# PCB_3U_BNC.net
KiCad netlist of a schematic drawn in Altium Designer
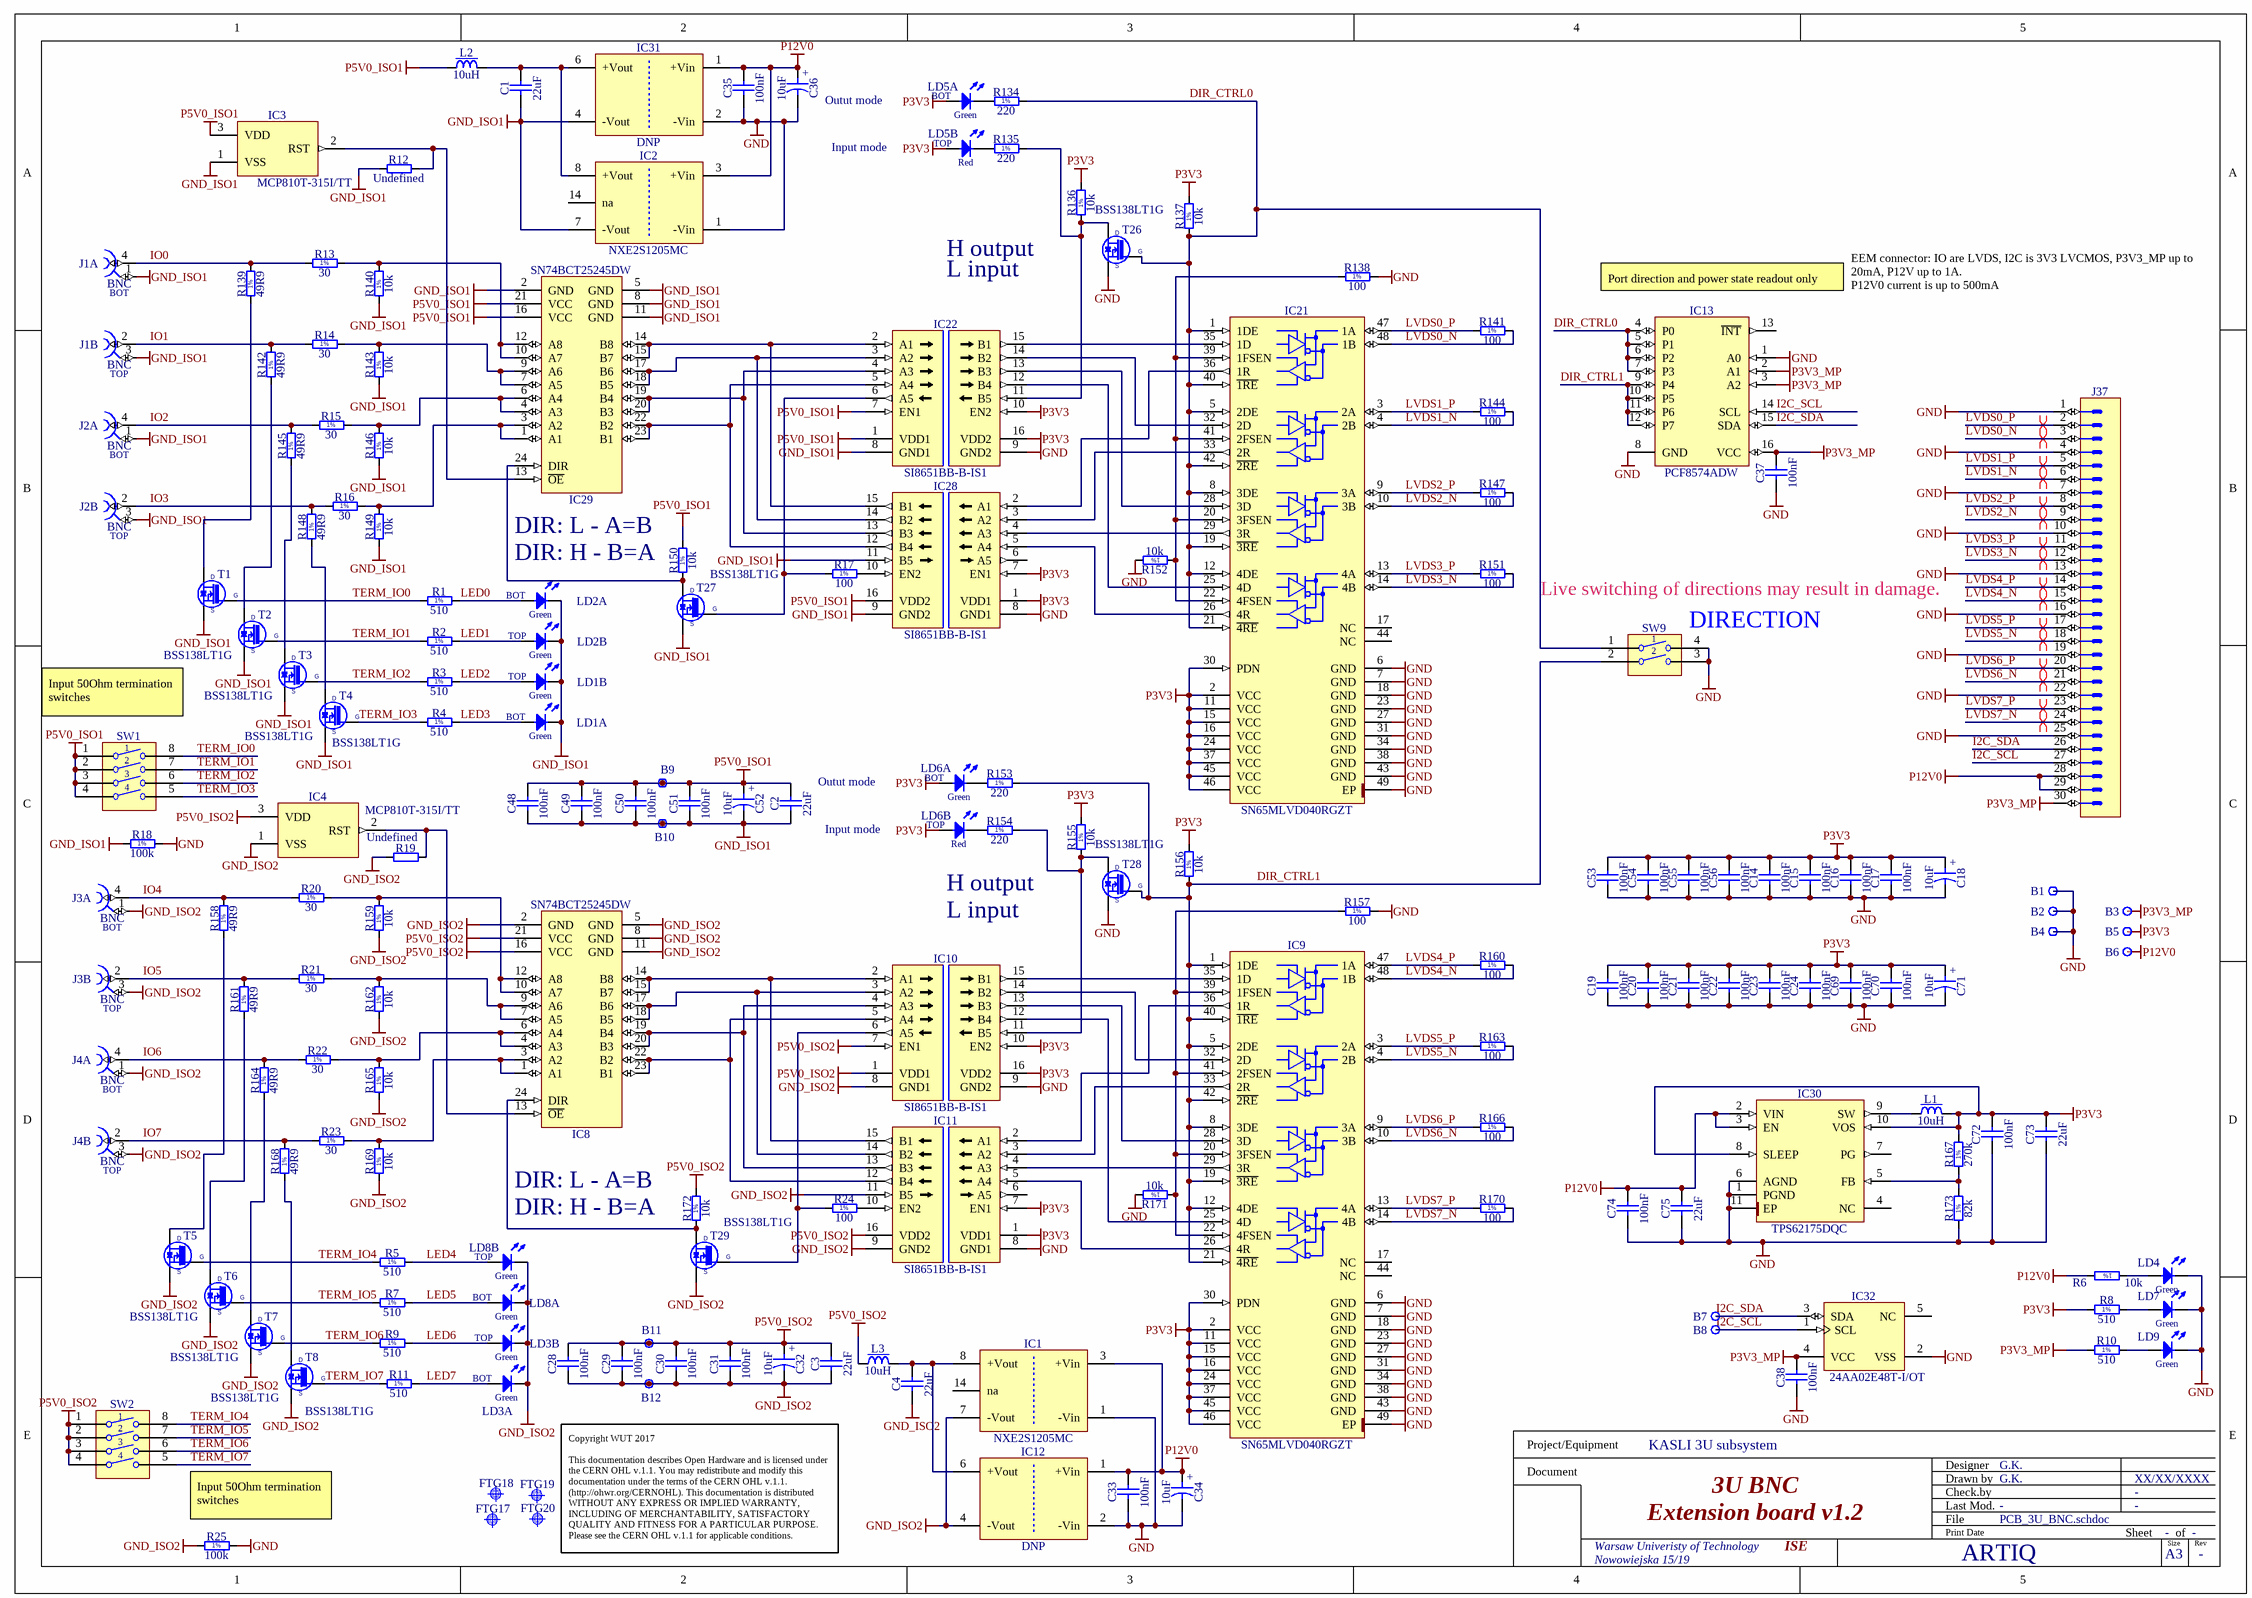
[diagram p0: PCB_3U_BNC.schdoc]

(export (version "E")
  (design (tool "Eeschema 10.0.6"))
  (components
    (comp (ref "B1")
      (value "Plated Hole")
      (footprint "c130h60")
      (description "Single Terminal Socket")
      (fields (field (name "PART NUMBER") "PLATED_HOLE0.6_PAD1.3") (field (name "AUTHOR") "CERN DEM MR"))
      (libsource (lib "Eletro-mechanical") (part "Single Terminal Socket"))
    )
    (comp (ref "B2")
      (value "Plated Hole")
      (footprint "c130h60")
      (description "Single Terminal Socket")
      (fields (field (name "PART NUMBER") "PLATED_HOLE0.6_PAD1.3") (field (name "AUTHOR") "CERN DEM MR"))
      (libsource (lib "Eletro-mechanical") (part "Single Terminal Socket"))
    )
    (comp (ref "B3")
      (value "Plated Hole")
      (footprint "c130h60")
      (description "Single Terminal Socket")
      (fields (field (name "PART NUMBER") "PLATED_HOLE0.6_PAD1.3") (field (name "AUTHOR") "CERN DEM MR"))
      (libsource (lib "Eletro-mechanical") (part "Single Terminal Socket"))
    )
    (comp (ref "B4")
      (value "Plated Hole")
      (footprint "c130h60")
      (description "Single Terminal Socket")
      (fields (field (name "PART NUMBER") "PLATED_HOLE0.6_PAD1.3") (field (name "AUTHOR") "CERN DEM MR"))
      (libsource (lib "Eletro-mechanical") (part "Single Terminal Socket"))
    )
    (comp (ref "B5")
      (value "Plated Hole")
      (footprint "c130h60")
      (description "Single Terminal Socket")
      (fields (field (name "PART NUMBER") "PLATED_HOLE0.6_PAD1.3") (field (name "AUTHOR") "CERN DEM MR"))
      (libsource (lib "Eletro-mechanical") (part "Single Terminal Socket"))
    )
    (comp (ref "B6")
      (value "Plated Hole")
      (footprint "c130h60")
      (description "Single Terminal Socket")
      (fields (field (name "PART NUMBER") "PLATED_HOLE0.6_PAD1.3") (field (name "AUTHOR") "CERN DEM MR"))
      (libsource (lib "Eletro-mechanical") (part "Single Terminal Socket"))
    )
    (comp (ref "B7")
      (value "Plated Hole")
      (footprint "c130h60")
      (description "Single Terminal Socket")
      (fields (field (name "PART NUMBER") "PLATED_HOLE0.6_PAD1.3") (field (name "AUTHOR") "CERN DEM MR"))
      (libsource (lib "Eletro-mechanical") (part "Single Terminal Socket"))
    )
    (comp (ref "B8")
      (value "Plated Hole")
      (footprint "c130h60")
      (description "Single Terminal Socket")
      (fields (field (name "PART NUMBER") "PLATED_HOLE0.6_PAD1.3") (field (name "AUTHOR") "CERN DEM MR"))
      (libsource (lib "Eletro-mechanical") (part "Single Terminal Socket"))
    )
    (comp (ref "B9")
      (value "Plated Hole")
      (footprint "c130h60")
      (description "Single Terminal Socket")
      (fields (field (name "PART NUMBER") "PLATED_HOLE0.6_PAD1.3") (field (name "AUTHOR") "CERN DEM MR"))
      (libsource (lib "Eletro-mechanical") (part "Single Terminal Socket"))
    )
    (comp (ref "B10")
      (value "Plated Hole")
      (footprint "c130h60")
      (description "Single Terminal Socket")
      (fields (field (name "PART NUMBER") "PLATED_HOLE0.6_PAD1.3") (field (name "AUTHOR") "CERN DEM MR"))
      (libsource (lib "Eletro-mechanical") (part "Single Terminal Socket"))
    )
    (comp (ref "B11")
      (value "Plated Hole")
      (footprint "c130h60")
      (description "Single Terminal Socket")
      (fields (field (name "PART NUMBER") "PLATED_HOLE0.6_PAD1.3") (field (name "AUTHOR") "CERN DEM MR"))
      (libsource (lib "Eletro-mechanical") (part "Single Terminal Socket"))
    )
    (comp (ref "B12")
      (value "Plated Hole")
      (footprint "c130h60")
      (description "Single Terminal Socket")
      (fields (field (name "PART NUMBER") "PLATED_HOLE0.6_PAD1.3") (field (name "AUTHOR") "CERN DEM MR"))
      (libsource (lib "Eletro-mechanical") (part "Single Terminal Socket"))
    )
    (comp (ref "C1")
      (value "22uF")
      (footprint "CAPC2012X135N")
      (description "Non-polarised capacitor")
      (fields
        (field (name "PART NUMBER") "CC0805_22UF_16V_10%_X5R")
        (field (name "VOLTAGE") "16V")
        (field (name "AUTHOR") "CERN DEM JLC")
      )
      (libsource (lib "Capacitors") (part "Capacitor - non polarized"))
    )
    (comp (ref "C2")
      (value "22uF")
      (footprint "CAPC2012X135N")
      (description "Non-polarised capacitor")
      (fields
        (field (name "PART NUMBER") "CC0805_22UF_16V_10%_X5R")
        (field (name "VOLTAGE") "16V")
        (field (name "AUTHOR") "CERN DEM JLC")
      )
      (libsource (lib "Capacitors") (part "Capacitor - non polarized"))
    )
    (comp (ref "C3")
      (value "22uF")
      (footprint "CAPC2012X135N")
      (description "Non-polarised capacitor")
      (fields
        (field (name "PART NUMBER") "CC0805_22UF_16V_10%_X5R")
        (field (name "VOLTAGE") "16V")
        (field (name "AUTHOR") "CERN DEM JLC")
      )
      (libsource (lib "Capacitors") (part "Capacitor - non polarized"))
    )
    (comp (ref "C4")
      (value "22uF")
      (footprint "CAPC2012X135N")
      (description "Non-polarised capacitor")
      (fields
        (field (name "PART NUMBER") "CC0805_22UF_16V_10%_X5R")
        (field (name "VOLTAGE") "16V")
        (field (name "AUTHOR") "CERN DEM JLC")
      )
      (libsource (lib "Capacitors") (part "Capacitor - non polarized"))
    )
    (comp (ref "C14")
      (value "100nF")
      (footprint "CAPC1005X55N")
      (description "Non-polarised capacitor")
      (fields
        (field (name "PART NUMBER") "CC0402_100NF_16V_10%_X5R")
        (field (name "VOLTAGE") "16V")
        (field (name "AUTHOR") "CERN DEM JLC")
      )
      (libsource (lib "Capacitors") (part "Capacitor - non polarized"))
    )
    (comp (ref "C15")
      (value "100nF")
      (footprint "CAPC1005X55N")
      (description "Non-polarised capacitor")
      (fields
        (field (name "PART NUMBER") "CC0402_100NF_16V_10%_X5R")
        (field (name "VOLTAGE") "16V")
        (field (name "AUTHOR") "CERN DEM JLC")
      )
      (libsource (lib "Capacitors") (part "Capacitor - non polarized"))
    )
    (comp (ref "C16")
      (value "100nF")
      (footprint "CAPC1005X55N")
      (description "Non-polarised capacitor")
      (fields
        (field (name "PART NUMBER") "CC0402_100NF_16V_10%_X5R")
        (field (name "VOLTAGE") "16V")
        (field (name "AUTHOR") "CERN DEM JLC")
      )
      (libsource (lib "Capacitors") (part "Capacitor - non polarized"))
    )
    (comp (ref "C17")
      (value "100nF")
      (footprint "CAPC1005X55N")
      (description "Non-polarised capacitor")
      (fields
        (field (name "PART NUMBER") "CC0402_100NF_16V_10%_X5R")
        (field (name "VOLTAGE") "16V")
        (field (name "AUTHOR") "CERN DEM JLC")
      )
      (libsource (lib "Capacitors") (part "Capacitor - non polarized"))
    )
    (comp (ref "C18")
      (value "10uF")
      (footprint "CAPAE430X540N")
      (description "Polarised capacitor")
      (fields
        (field (name "PART NUMBER") "CAE430-540_10UF_16V_20%")
        (field (name "VOLTAGE") "16V")
        (field (name "AUTHOR") "CERN DEM JLC")
      )
      (libsource (lib "Capacitors") (part "Capacitor - polarized"))
    )
    (comp (ref "C19")
      (value "100nF")
      (footprint "CAPC1005X55N")
      (description "Non-polarised capacitor")
      (fields
        (field (name "PART NUMBER") "CC0402_100NF_16V_10%_X5R")
        (field (name "VOLTAGE") "16V")
        (field (name "AUTHOR") "CERN DEM JLC")
      )
      (libsource (lib "Capacitors") (part "Capacitor - non polarized"))
    )
    (comp (ref "C20")
      (value "100nF")
      (footprint "CAPC1005X55N")
      (description "Non-polarised capacitor")
      (fields
        (field (name "PART NUMBER") "CC0402_100NF_16V_10%_X5R")
        (field (name "VOLTAGE") "16V")
        (field (name "AUTHOR") "CERN DEM JLC")
      )
      (libsource (lib "Capacitors") (part "Capacitor - non polarized"))
    )
    (comp (ref "C21")
      (value "100nF")
      (footprint "CAPC1005X55N")
      (description "Non-polarised capacitor")
      (fields
        (field (name "PART NUMBER") "CC0402_100NF_16V_10%_X5R")
        (field (name "VOLTAGE") "16V")
        (field (name "AUTHOR") "CERN DEM JLC")
      )
      (libsource (lib "Capacitors") (part "Capacitor - non polarized"))
    )
    (comp (ref "C22")
      (value "100nF")
      (footprint "CAPC1005X55N")
      (description "Non-polarised capacitor")
      (fields
        (field (name "PART NUMBER") "CC0402_100NF_16V_10%_X5R")
        (field (name "VOLTAGE") "16V")
        (field (name "AUTHOR") "CERN DEM JLC")
      )
      (libsource (lib "Capacitors") (part "Capacitor - non polarized"))
    )
    (comp (ref "C23")
      (value "100nF")
      (footprint "CAPC1005X55N")
      (description "Non-polarised capacitor")
      (fields
        (field (name "PART NUMBER") "CC0402_100NF_16V_10%_X5R")
        (field (name "VOLTAGE") "16V")
        (field (name "AUTHOR") "CERN DEM JLC")
      )
      (libsource (lib "Capacitors") (part "Capacitor - non polarized"))
    )
    (comp (ref "C24")
      (value "100nF")
      (footprint "CAPC1005X55N")
      (description "Non-polarised capacitor")
      (fields
        (field (name "PART NUMBER") "CC0402_100NF_16V_10%_X5R")
        (field (name "VOLTAGE") "16V")
        (field (name "AUTHOR") "CERN DEM JLC")
      )
      (libsource (lib "Capacitors") (part "Capacitor - non polarized"))
    )
    (comp (ref "C28")
      (value "100nF")
      (footprint "CAPC1005X55N")
      (description "Non-polarised capacitor")
      (fields
        (field (name "PART NUMBER") "CC0402_100NF_16V_10%_X5R")
        (field (name "VOLTAGE") "16V")
        (field (name "AUTHOR") "CERN DEM JLC")
      )
      (libsource (lib "Capacitors") (part "Capacitor - non polarized"))
    )
    (comp (ref "C29")
      (value "100nF")
      (footprint "CAPC1005X55N")
      (description "Non-polarised capacitor")
      (fields
        (field (name "PART NUMBER") "CC0402_100NF_16V_10%_X5R")
        (field (name "VOLTAGE") "16V")
        (field (name "AUTHOR") "CERN DEM JLC")
      )
      (libsource (lib "Capacitors") (part "Capacitor - non polarized"))
    )
    (comp (ref "C30")
      (value "100nF")
      (footprint "CAPC1005X55N")
      (description "Non-polarised capacitor")
      (fields
        (field (name "PART NUMBER") "CC0402_100NF_16V_10%_X5R")
        (field (name "VOLTAGE") "16V")
        (field (name "AUTHOR") "CERN DEM JLC")
      )
      (libsource (lib "Capacitors") (part "Capacitor - non polarized"))
    )
    (comp (ref "C31")
      (value "100nF")
      (footprint "CAPC1005X55N")
      (description "Non-polarised capacitor")
      (fields
        (field (name "PART NUMBER") "CC0402_100NF_16V_10%_X5R")
        (field (name "VOLTAGE") "16V")
        (field (name "AUTHOR") "CERN DEM JLC")
      )
      (libsource (lib "Capacitors") (part "Capacitor - non polarized"))
    )
    (comp (ref "C32")
      (value "10uF")
      (footprint "CAPAE430X540N")
      (description "Polarised capacitor")
      (fields
        (field (name "PART NUMBER") "CAE430-540_10UF_16V_20%")
        (field (name "VOLTAGE") "16V")
        (field (name "AUTHOR") "CERN DEM JLC")
      )
      (libsource (lib "Capacitors") (part "Capacitor - polarized"))
    )
    (comp (ref "C33")
      (value "100nF")
      (footprint "CAPC1005X55N")
      (description "Non-polarised capacitor")
      (fields
        (field (name "PART NUMBER") "CC0402_100NF_16V_10%_X5R")
        (field (name "VOLTAGE") "16V")
        (field (name "AUTHOR") "CERN DEM JLC")
      )
      (libsource (lib "Capacitors") (part "Capacitor - non polarized"))
    )
    (comp (ref "C34")
      (value "10uF")
      (footprint "CAPAE430X540N")
      (description "Polarised capacitor")
      (fields
        (field (name "PART NUMBER") "CAE430-540_10UF_16V_20%")
        (field (name "VOLTAGE") "16V")
        (field (name "AUTHOR") "CERN DEM JLC")
      )
      (libsource (lib "Capacitors") (part "Capacitor - polarized"))
    )
    (comp (ref "C35")
      (value "100nF")
      (footprint "CAPC1005X55N")
      (description "Non-polarised capacitor")
      (fields
        (field (name "PART NUMBER") "CC0402_100NF_16V_10%_X5R")
        (field (name "VOLTAGE") "16V")
        (field (name "AUTHOR") "CERN DEM JLC")
      )
      (libsource (lib "Capacitors") (part "Capacitor - non polarized"))
    )
    (comp (ref "C36")
      (value "10uF")
      (footprint "CAPAE430X540N")
      (description "Polarised capacitor")
      (fields
        (field (name "PART NUMBER") "CAE430-540_10UF_16V_20%")
        (field (name "VOLTAGE") "16V")
        (field (name "AUTHOR") "CERN DEM JLC")
      )
      (libsource (lib "Capacitors") (part "Capacitor - polarized"))
    )
    (comp (ref "C37")
      (value "100nF")
      (footprint "CAPC1005X55N")
      (description "Non-polarised capacitor")
      (fields
        (field (name "PART NUMBER") "CC0402_100NF_16V_10%_X5R")
        (field (name "VOLTAGE") "16V")
        (field (name "AUTHOR") "CERN DEM JLC")
      )
      (libsource (lib "Capacitors") (part "Capacitor - non polarized"))
    )
    (comp (ref "C38")
      (value "100nF")
      (footprint "CAPC1005X55N")
      (description "Non-polarised capacitor")
      (fields
        (field (name "PART NUMBER") "CC0402_100NF_16V_10%_X5R")
        (field (name "VOLTAGE") "16V")
        (field (name "AUTHOR") "CERN DEM JLC")
      )
      (libsource (lib "Capacitors") (part "Capacitor - non polarized"))
    )
    (comp (ref "C48")
      (value "100nF")
      (footprint "CAPC1005X55N")
      (description "Non-polarised capacitor")
      (fields
        (field (name "PART NUMBER") "CC0402_100NF_16V_10%_X5R")
        (field (name "VOLTAGE") "16V")
        (field (name "AUTHOR") "CERN DEM JLC")
      )
      (libsource (lib "Capacitors") (part "Capacitor - non polarized"))
    )
    (comp (ref "C49")
      (value "100nF")
      (footprint "CAPC1005X55N")
      (description "Non-polarised capacitor")
      (fields
        (field (name "PART NUMBER") "CC0402_100NF_16V_10%_X5R")
        (field (name "VOLTAGE") "16V")
        (field (name "AUTHOR") "CERN DEM JLC")
      )
      (libsource (lib "Capacitors") (part "Capacitor - non polarized"))
    )
    (comp (ref "C50")
      (value "100nF")
      (footprint "CAPC1005X55N")
      (description "Non-polarised capacitor")
      (fields
        (field (name "PART NUMBER") "CC0402_100NF_16V_10%_X5R")
        (field (name "VOLTAGE") "16V")
        (field (name "AUTHOR") "CERN DEM JLC")
      )
      (libsource (lib "Capacitors") (part "Capacitor - non polarized"))
    )
    (comp (ref "C51")
      (value "100nF")
      (footprint "CAPC1005X55N")
      (description "Non-polarised capacitor")
      (fields
        (field (name "PART NUMBER") "CC0402_100NF_16V_10%_X5R")
        (field (name "VOLTAGE") "16V")
        (field (name "AUTHOR") "CERN DEM JLC")
      )
      (libsource (lib "Capacitors") (part "Capacitor - non polarized"))
    )
    (comp (ref "C52")
      (value "10uF")
      (footprint "CAPAE430X540N")
      (description "Polarised capacitor")
      (fields
        (field (name "PART NUMBER") "CAE430-540_10UF_16V_20%")
        (field (name "VOLTAGE") "16V")
        (field (name "AUTHOR") "CERN DEM JLC")
      )
      (libsource (lib "Capacitors") (part "Capacitor - polarized"))
    )
    (comp (ref "C53")
      (value "100nF")
      (footprint "CAPC1005X55N")
      (description "Non-polarised capacitor")
      (fields
        (field (name "PART NUMBER") "CC0402_100NF_16V_10%_X5R")
        (field (name "VOLTAGE") "16V")
        (field (name "AUTHOR") "CERN DEM JLC")
      )
      (libsource (lib "Capacitors") (part "Capacitor - non polarized"))
    )
    (comp (ref "C54")
      (value "100nF")
      (footprint "CAPC1005X55N")
      (description "Non-polarised capacitor")
      (fields
        (field (name "PART NUMBER") "CC0402_100NF_16V_10%_X5R")
        (field (name "VOLTAGE") "16V")
        (field (name "AUTHOR") "CERN DEM JLC")
      )
      (libsource (lib "Capacitors") (part "Capacitor - non polarized"))
    )
    (comp (ref "C55")
      (value "100nF")
      (footprint "CAPC1005X55N")
      (description "Non-polarised capacitor")
      (fields
        (field (name "PART NUMBER") "CC0402_100NF_16V_10%_X5R")
        (field (name "VOLTAGE") "16V")
        (field (name "AUTHOR") "CERN DEM JLC")
      )
      (libsource (lib "Capacitors") (part "Capacitor - non polarized"))
    )
    (comp (ref "C56")
      (value "100nF")
      (footprint "CAPC1005X55N")
      (description "Non-polarised capacitor")
      (fields
        (field (name "PART NUMBER") "CC0402_100NF_16V_10%_X5R")
        (field (name "VOLTAGE") "16V")
        (field (name "AUTHOR") "CERN DEM JLC")
      )
      (libsource (lib "Capacitors") (part "Capacitor - non polarized"))
    )
    (comp (ref "C69")
      (value "100nF")
      (footprint "CAPC1005X55N")
      (description "Non-polarised capacitor")
      (fields
        (field (name "PART NUMBER") "CC0402_100NF_16V_10%_X5R")
        (field (name "VOLTAGE") "16V")
        (field (name "AUTHOR") "CERN DEM JLC")
      )
      (libsource (lib "Capacitors") (part "Capacitor - non polarized"))
    )
    (comp (ref "C70")
      (value "100nF")
      (footprint "CAPC1005X55N")
      (description "Non-polarised capacitor")
      (fields
        (field (name "PART NUMBER") "CC0402_100NF_16V_10%_X5R")
        (field (name "VOLTAGE") "16V")
        (field (name "AUTHOR") "CERN DEM JLC")
      )
      (libsource (lib "Capacitors") (part "Capacitor - non polarized"))
    )
    (comp (ref "C71")
      (value "10uF")
      (footprint "CAPAE430X540N")
      (description "Polarised capacitor")
      (fields
        (field (name "PART NUMBER") "CAE430-540_10UF_16V_20%")
        (field (name "VOLTAGE") "16V")
        (field (name "AUTHOR") "CERN DEM JLC")
      )
      (libsource (lib "Capacitors") (part "Capacitor - polarized"))
    )
    (comp (ref "C72")
      (value "100nF")
      (footprint "CAPC1005X55N")
      (description "Non-polarised capacitor")
      (fields
        (field (name "PART NUMBER") "CC0402_100NF_16V_10%_X5R")
        (field (name "VOLTAGE") "16V")
        (field (name "AUTHOR") "CERN DEM JLC")
      )
      (libsource (lib "Capacitors") (part "Capacitor - non polarized"))
    )
    (comp (ref "C73")
      (value "22uF")
      (footprint "CAPC2012X135N")
      (description "Non-polarised capacitor")
      (fields
        (field (name "PART NUMBER") "CC0805_22UF_16V_10%_X5R")
        (field (name "VOLTAGE") "16V")
        (field (name "AUTHOR") "CERN DEM JLC")
      )
      (libsource (lib "Capacitors") (part "Capacitor - non polarized"))
    )
    (comp (ref "C74")
      (value "100nF")
      (footprint "CAPC1005X55N")
      (description "Non-polarised capacitor")
      (fields
        (field (name "PART NUMBER") "CC0402_100NF_16V_10%_X5R")
        (field (name "VOLTAGE") "16V")
        (field (name "AUTHOR") "CERN DEM JLC")
      )
      (libsource (lib "Capacitors") (part "Capacitor - non polarized"))
    )
    (comp (ref "C75")
      (value "22uF")
      (footprint "CAPC2012X135N")
      (description "Non-polarised capacitor")
      (fields
        (field (name "PART NUMBER") "CC0805_22UF_16V_10%_X5R")
        (field (name "VOLTAGE") "16V")
        (field (name "AUTHOR") "CERN DEM JLC")
      )
      (libsource (lib "Capacitors") (part "Capacitor - non polarized"))
    )
    (comp (ref "FTG17")
      (value "Use only in PCB")
      (footprint "FIDUCIAL_TOP_C100-200")
      (description "Fiducial Target")
      (fields (field (name "PART NUMBER") "FIDUCIAL_TARGET_C100-200") (field (name "AUTHOR") "CERN DEM JLC"))
      (libsource (lib "Eletro-mechanical") (part "Fiducial Target"))
    )
    (comp (ref "FTG18")
      (value "Use only in PCB")
      (footprint "FIDUCIAL_TOP_S100-200")
      (description "Fiducial Target")
      (fields (field (name "PART NUMBER") "FIDUCIAL_TARGET_S100-200") (field (name "AUTHOR") "CERN DEM JLC"))
      (libsource (lib "Eletro-mechanical") (part "Fiducial Target"))
    )
    (comp (ref "FTG19")
      (value "Use only in PCB")
      (footprint "FIDUCIAL_TOP_S200-400")
      (description "Fiducial Target")
      (fields (field (name "PART NUMBER") "FIDUCIAL_TARGET_S200-400") (field (name "AUTHOR") "CERN DEM JLC"))
      (libsource (lib "Eletro-mechanical") (part "Fiducial Target"))
    )
    (comp (ref "FTG20")
      (value "Use only in PCB")
      (footprint "FIDUCIAL_TOP_S100-200")
      (description "Fiducial Target")
      (fields (field (name "PART NUMBER") "FIDUCIAL_TARGET_S100-200") (field (name "AUTHOR") "CERN DEM JLC"))
      (libsource (lib "Eletro-mechanical") (part "Fiducial Target"))
    )
    (comp (ref "IC1")
      (value "NXE2S1205MC")
      (footprint "DCDC_MURATA_NXE2")
      (description "MURATA, NXE2 Serie, Dual Output DCDC Converter")
      (fields (field (name "MANUFACTURER") "MURATA POWER SOLUTIONS") (field (name "AUTHOR") "CERN DEM MR"))
      (libsource (lib "LIBRARY_SCH") (part "DCDC_MURATA_NXE2S1205MC"))
    )
    (comp (ref "IC2")
      (value "NXE2S1205MC")
      (footprint "DCDC_MURATA_NXE2")
      (description "MURATA, NXE2 Serie, Dual Output DCDC Converter")
      (fields (field (name "MANUFACTURER") "MURATA POWER SOLUTIONS") (field (name "AUTHOR") "CERN DEM MR"))
      (libsource (lib "LIBRARY_SCH") (part "DCDC_MURATA_NXE2S1205MC"))
    )
    (comp (ref "IC3")
      (value "MCP810T-315I/TT")
      (footprint "SOT95P237X112-3N")
      (description "3.075V Microcontroller Supervisory Circuit With Push-Pull Output")
      (fields (field (name "MANUFACTURER") "MICROCHIP TECHNOLOGY") (field (name "AUTHOR") "GK"))
      (libsource (lib "LIBRARY_SCH") (part "VMON_MCP810"))
    )
    (comp (ref "IC4")
      (value "MCP810T-315I/TT")
      (footprint "SOT95P237X112-3N")
      (description "3.075V Microcontroller Supervisory Circuit With Push-Pull Output")
      (fields (field (name "MANUFACTURER") "MICROCHIP TECHNOLOGY") (field (name "AUTHOR") "GK"))
      (libsource (lib "LIBRARY_SCH") (part "VMON_MCP810"))
    )
    (comp (ref "IC8")
      (value "SN74BCT25245DW")
      (footprint "SOIC127P1030X265-24N")
      (description "25 Ohms Octal Bus Transceiver With 3-State Outputs")
      (fields (field (name "MANUFACTURER") "TEXAS INSTRUMENTS") (field (name "AUTHOR") "CERN DEM JLC"))
      (libsource (lib "ICs And Semiconductors") (part "7425245"))
    )
    (comp (ref "IC9")
      (value "SN65MLVD040RGZT")
      (footprint "QFN50P700X700X100-49N-S420")
      (description "4-Channel Half-Duplex M-LVDS Line Transceiver")
      (fields (field (name "MANUFACTURER") "TEXAS INSTRUMENTS") (field (name "AUTHOR") "CERN DEM JLC"))
      (libsource (lib "ICs And Semiconductors") (part "SN65MLVD040"))
    )
    (comp (ref "IC10")
      (value "SI8651BB-B-IS1")
      (footprint "SOIC127P600X175-16N")
      (description "Low Power Five-Channel Digital Isolator")
      (fields (field (name "MANUFACTURER") "SILICON LABS") (field (name "AUTHOR") "CERN DEM JLC"))
      (libsource (lib "ICs And Semiconductors") (part "Si8651"))
    )
    (comp (ref "IC11")
      (value "SI8651BB-B-IS1")
      (footprint "SOIC127P600X175-16N")
      (description "Low Power Five-Channel Digital Isolator")
      (fields (field (name "MANUFACTURER") "SILICON LABS") (field (name "AUTHOR") "CERN DEM JLC"))
      (libsource (lib "") (part "Si8651_1"))
    )
    (comp (ref "IC12")
      (value "DNP")
      (footprint "DCDC_TRACO_TMA")
      (description "1 W Watt, 10.8-13.2VDCVin, 5 V@0.2 A")
      (fields
        (field (name "PART NUMBER") "TMA 1205S")
        (field (name "MANUFACTURER") "TRACO POWER")
        (field (name "AUTHOR") "GK")
      )
      (libsource (lib "LIBRARY_SCH") (part "DC/DC_TRACO_TMA1205S"))
    )
    (comp (ref "IC13")
      (value "PCF8574ADW")
      (footprint "SOIC127P1030X265-16N")
      (description "Remote 8-bit I/O Expander For I2C Bus")
      (fields (field (name "MANUFACTURER") "TEXAS INSTRUMENTS") (field (name "AUTHOR") "CERN DEM JLC"))
      (libsource (lib "ICs And Semiconductors") (part "PCF8574ADW"))
    )
    (comp (ref "IC21")
      (value "SN65MLVD040RGZT")
      (footprint "QFN50P700X700X100-49N-S420")
      (description "4-Channel Half-Duplex M-LVDS Line Transceiver")
      (fields (field (name "MANUFACTURER") "TEXAS INSTRUMENTS") (field (name "AUTHOR") "CERN DEM JLC"))
      (libsource (lib "ICs And Semiconductors") (part "SN65MLVD040"))
    )
    (comp (ref "IC22")
      (value "SI8651BB-B-IS1")
      (footprint "SOIC127P600X175-16N")
      (description "Low Power Five-Channel Digital Isolator")
      (fields (field (name "MANUFACTURER") "SILICON LABS") (field (name "AUTHOR") "CERN DEM JLC"))
      (libsource (lib "ICs And Semiconductors") (part "Si8651"))
    )
    (comp (ref "IC28")
      (value "SI8651BB-B-IS1")
      (footprint "SOIC127P600X175-16N")
      (description "Low Power Five-Channel Digital Isolator")
      (fields (field (name "MANUFACTURER") "SILICON LABS") (field (name "AUTHOR") "CERN DEM JLC"))
      (libsource (lib "") (part "Si8651_1"))
    )
    (comp (ref "IC29")
      (value "SN74BCT25245DW")
      (footprint "SOIC127P1030X265-24N")
      (description "25 Ohms Octal Bus Transceiver With 3-State Outputs")
      (fields (field (name "MANUFACTURER") "TEXAS INSTRUMENTS") (field (name "AUTHOR") "CERN DEM JLC"))
      (libsource (lib "ICs And Semiconductors") (part "7425245"))
    )
    (comp (ref "IC30")
      (value "TPS62175DQC")
      (footprint "SON50P200X300X80-11N-R94X250")
      (description "4.75-28VDC to 1-6VDC, 500mA Step-Down Converter With Sleep Mode")
      (fields (field (name "MANUFACTURER") "TEXAS INSTRUMENTS") (field (name "AUTHOR") "CERN DEM JMW"))
      (libsource (lib "ICs And Semiconductors") (part "TPS62175"))
    )
    (comp (ref "IC31")
      (value "DNP")
      (footprint "DCDC_TRACO_TMA")
      (description "1 W Watt, 10.8-13.2VDCVin, 5 V@0.2 A")
      (fields
        (field (name "PART NUMBER") "TMA 1205S")
        (field (name "MANUFACTURER") "TRACO POWER")
        (field (name "AUTHOR") "GK")
      )
      (libsource (lib "LIBRARY_SCH") (part "DC/DC_TRACO_TMA1205S"))
    )
    (comp (ref "IC32")
      (value "24AA02E48T-I/OT")
      (footprint "SOT95P280X145-5N")
      (description "1.7V-5.5V, 2K I2C Serial EEPROM With EUI-48 Node Identity")
      (fields (field (name "MANUFACTURER") "MICROCHIP TECHNOLOGY") (field (name "AUTHOR") "CERN DEM MR"))
      (libsource (lib "ICs And Semiconductors") (part "24AA02E48T-I/OT"))
    )
    (comp (ref "J1")
      (value "BNC")
      (footprint "RENHOTEC_RHT-610-0049")
      (description "Dual Right Angle 50 Ohm BNC Jack, White Valox Case")
      (fields
        (field (name "PART NUMBER") "RENHOTEC_RHT-610-0049")
        (field (name "MANUFACTURER") "RENHOTEC")
        (field (name "AUTHOR") "GK")
      )
      (libsource (lib "LIBRARY_SCH") (part "CON_BNC_DUAL"))
    )
    (comp (ref "J2")
      (value "BNC")
      (footprint "RENHOTEC_RHT-610-0049")
      (description "Dual Right Angle 50 Ohm BNC Jack, White Valox Case")
      (fields
        (field (name "PART NUMBER") "RENHOTEC_RHT-610-0049")
        (field (name "MANUFACTURER") "RENHOTEC")
        (field (name "AUTHOR") "GK")
      )
      (libsource (lib "LIBRARY_SCH") (part "CON_BNC_DUAL"))
    )
    (comp (ref "J3")
      (value "BNC")
      (footprint "RENHOTEC_RHT-610-0049")
      (description "Dual Right Angle 50 Ohm BNC Jack, White Valox Case")
      (fields
        (field (name "PART NUMBER") "RENHOTEC_RHT-610-0049")
        (field (name "MANUFACTURER") "RENHOTEC")
        (field (name "AUTHOR") "GK")
      )
      (libsource (lib "LIBRARY_SCH") (part "CON_BNC_DUAL"))
    )
    (comp (ref "J4")
      (value "BNC")
      (footprint "RENHOTEC_RHT-610-0049")
      (description "Dual Right Angle 50 Ohm BNC Jack, White Valox Case")
      (fields
        (field (name "PART NUMBER") "RENHOTEC_RHT-610-0049")
        (field (name "MANUFACTURER") "RENHOTEC")
        (field (name "AUTHOR") "GK")
      )
      (libsource (lib "LIBRARY_SCH") (part "CON_BNC_DUAL"))
    )
    (comp (ref "J37")
      (value "~")
      (footprint "3M_N2530-6002RB")
      (description "Connector 30 Male")
      (fields
        (field (name "PART NUMBER") "3M_N2530-6002RB")
        (field (name "MANUFACTURER") "3M")
        (field (name "AUTHOR") "CERN DEM JLC")
      )
      (libsource (lib "Connectors") (part "Connector 30 Male"))
    )
    (comp (ref "L1")
      (value "10uH")
      (footprint "IND_MURATA-PS_8400")
      (description "Inductor With Core")
      (fields
        (field (name "PART NUMBER") "IND_10UH_10%_MURATA-PS_8400")
        (field (name "POWER") "950mA")
        (field (name "AUTHOR") "CERN DEM JLC")
      )
      (libsource (lib "Inductors & Transformers") (part "Inductor With Magnetic core"))
    )
    (comp (ref "L2")
      (value "10uH")
      (footprint "IND_MURATA-PS_8400")
      (description "Inductor With Core")
      (fields
        (field (name "PART NUMBER") "IND_10UH_10%_MURATA-PS_8400")
        (field (name "POWER") "950mA")
        (field (name "AUTHOR") "CERN DEM JLC")
      )
      (libsource (lib "Inductors & Transformers") (part "Inductor With Magnetic core"))
    )
    (comp (ref "L3")
      (value "10uH")
      (footprint "IND_MURATA-PS_8400")
      (description "Inductor With Core")
      (fields
        (field (name "PART NUMBER") "IND_10UH_10%_MURATA-PS_8400")
        (field (name "POWER") "950mA")
        (field (name "AUTHOR") "CERN DEM JLC")
      )
      (libsource (lib "Inductors & Transformers") (part "Inductor With Magnetic core"))
    )
    (comp (ref "LD1")
      (value "Green/Green")
      (footprint "LED_DIALIGHT_571-0122F")
      (description "LED x2 Green 1C2A-BOT_3C4A-TOP")
      (fields
        (field (name "PART NUMBER") "LED_DIALIGHT_571-0122F")
        (field (name "MANUFACTURER") "DIALIGHT")
        (field (name "AUTHOR") "CERN DEM JLC")
      )
      (libsource (lib "ICs And Semiconductors") (part "LED x2 Green 1C2A-BOT_3C4A-TOP"))
    )
    (comp (ref "LD2")
      (value "Green/Green")
      (footprint "LED_DIALIGHT_571-0122F")
      (description "LED x2 Green 1C2A-BOT_3C4A-TOP")
      (fields
        (field (name "PART NUMBER") "LED_DIALIGHT_571-0122F")
        (field (name "MANUFACTURER") "DIALIGHT")
        (field (name "AUTHOR") "CERN DEM JLC")
      )
      (libsource (lib "ICs And Semiconductors") (part "LED x2 Green 1C2A-BOT_3C4A-TOP"))
    )
    (comp (ref "LD3")
      (value "Green/Green")
      (footprint "LED_DIALIGHT_571-0122F")
      (description "LED x2 Green 1C2A-BOT_3C4A-TOP")
      (fields
        (field (name "PART NUMBER") "LED_DIALIGHT_571-0122F")
        (field (name "MANUFACTURER") "DIALIGHT")
        (field (name "AUTHOR") "CERN DEM JLC")
      )
      (libsource (lib "ICs And Semiconductors") (part "LED x2 Green 1C2A-BOT_3C4A-TOP"))
    )
    (comp (ref "LD4")
      (value "Green")
      (footprint "LED_KINGBRIGHT_KPH-1608CGCK")
      (description "LED Green 1C 2A")
      (fields
        (field (name "PART NUMBER") "LED_KINGBRIGHT_KPH-1608CGCK")
        (field (name "MANUFACTURER") "KINGBRIGHT")
        (field (name "AUTHOR") "CERN DEM JLC")
      )
      (libsource (lib "ICs And Semiconductors") (part "LED Green 1C 2A"))
    )
    (comp (ref "LD5")
      (value "Red/Green")
      (footprint "LED_DIALIGHT_571-0112F")
      (description "2x LED  Botom Green, Top Red")
      (fields
        (field (name "PART NUMBER") "LED_DIALIGHT_571-0112F")
        (field (name "MANUFACTURER") "DIALIGHT")
        (field (name "AUTHOR") "CERN DEM JLC")
      )
      (libsource (lib "ICs And Semiconductors") (part "LED x2 G-1C2A-BOT_R-3C4A-TOP"))
    )
    (comp (ref "LD6")
      (value "Red/Green")
      (footprint "LED_DIALIGHT_571-0112F")
      (description "2x LED  Botom Green, Top Red")
      (fields
        (field (name "PART NUMBER") "LED_DIALIGHT_571-0112F")
        (field (name "MANUFACTURER") "DIALIGHT")
        (field (name "AUTHOR") "CERN DEM JLC")
      )
      (libsource (lib "ICs And Semiconductors") (part "LED x2 G-1C2A-BOT_R-3C4A-TOP"))
    )
    (comp (ref "LD7")
      (value "Green")
      (footprint "LED_KINGBRIGHT_KPH-1608CGCK")
      (description "LED Green 1C 2A")
      (fields
        (field (name "PART NUMBER") "LED_KINGBRIGHT_KPH-1608CGCK")
        (field (name "MANUFACTURER") "KINGBRIGHT")
        (field (name "AUTHOR") "CERN DEM JLC")
      )
      (libsource (lib "ICs And Semiconductors") (part "LED Green 1C 2A"))
    )
    (comp (ref "LD8")
      (value "Green/Green")
      (footprint "LED_DIALIGHT_571-0122F")
      (description "LED x2 Green 1C2A-BOT_3C4A-TOP")
      (fields
        (field (name "PART NUMBER") "LED_DIALIGHT_571-0122F")
        (field (name "MANUFACTURER") "DIALIGHT")
        (field (name "AUTHOR") "CERN DEM JLC")
      )
      (libsource (lib "ICs And Semiconductors") (part "LED x2 Green 1C2A-BOT_3C4A-TOP"))
    )
    (comp (ref "LD9")
      (value "Green")
      (footprint "LED_KINGBRIGHT_KPH-1608CGCK")
      (description "LED Green 1C 2A")
      (fields
        (field (name "PART NUMBER") "LED_KINGBRIGHT_KPH-1608CGCK")
        (field (name "MANUFACTURER") "KINGBRIGHT")
        (field (name "AUTHOR") "CERN DEM JLC")
      )
      (libsource (lib "ICs And Semiconductors") (part "LED Green 1C 2A"))
    )
    (comp (ref "R1")
      (value "510")
      (footprint "RESC1005X40N")
      (description "Resistor - 1%")
      (fields
        (field (name "PART NUMBER") "R0402_510R_1%_0.0625W_100PPM")
        (field (name "POWER") "0.0625W")
        (field (name "AUTHOR") "CERN DEM JLC")
      )
      (libsource (lib "Resistors") (part "Resistor - 1%"))
    )
    (comp (ref "R2")
      (value "510")
      (footprint "RESC1005X40N")
      (description "Resistor - 1%")
      (fields
        (field (name "PART NUMBER") "R0402_510R_1%_0.0625W_100PPM")
        (field (name "POWER") "0.0625W")
        (field (name "AUTHOR") "CERN DEM JLC")
      )
      (libsource (lib "Resistors") (part "Resistor - 1%"))
    )
    (comp (ref "R3")
      (value "510")
      (footprint "RESC1005X40N")
      (description "Resistor - 1%")
      (fields
        (field (name "PART NUMBER") "R0402_510R_1%_0.0625W_100PPM")
        (field (name "POWER") "0.0625W")
        (field (name "AUTHOR") "CERN DEM JLC")
      )
      (libsource (lib "Resistors") (part "Resistor - 1%"))
    )
    (comp (ref "R4")
      (value "510")
      (footprint "RESC1005X40N")
      (description "Resistor - 1%")
      (fields
        (field (name "PART NUMBER") "R0402_510R_1%_0.0625W_100PPM")
        (field (name "POWER") "0.0625W")
        (field (name "AUTHOR") "CERN DEM JLC")
      )
      (libsource (lib "Resistors") (part "Resistor - 1%"))
    )
    (comp (ref "R5")
      (value "510")
      (footprint "RESC1005X40N")
      (description "Resistor - 1%")
      (fields
        (field (name "PART NUMBER") "R0402_510R_1%_0.0625W_100PPM")
        (field (name "POWER") "0.0625W")
        (field (name "AUTHOR") "CERN DEM JLC")
      )
      (libsource (lib "Resistors") (part "Resistor - 1%"))
    )
    (comp (ref "R6")
      (value "10k")
      (footprint "RESC1005X40N")
      (description "Resistor - 1%")
      (fields
        (field (name "PART NUMBER") "R0402_10K_1%_0.0625W_100PPM")
        (field (name "POWER") "0.0625W")
        (field (name "AUTHOR") "CERN DEM JLC")
      )
      (libsource (lib "Resistors") (part "Resistor - 1%"))
    )
    (comp (ref "R7")
      (value "510")
      (footprint "RESC1005X40N")
      (description "Resistor - 1%")
      (fields
        (field (name "PART NUMBER") "R0402_510R_1%_0.0625W_100PPM")
        (field (name "POWER") "0.0625W")
        (field (name "AUTHOR") "CERN DEM JLC")
      )
      (libsource (lib "Resistors") (part "Resistor - 1%"))
    )
    (comp (ref "R8")
      (value "510")
      (footprint "RESC1005X40N")
      (description "Resistor - 1%")
      (fields
        (field (name "PART NUMBER") "R0402_510R_1%_0.0625W_100PPM")
        (field (name "POWER") "0.0625W")
        (field (name "AUTHOR") "CERN DEM JLC")
      )
      (libsource (lib "Resistors") (part "Resistor - 1%"))
    )
    (comp (ref "R9")
      (value "510")
      (footprint "RESC1005X40N")
      (description "Resistor - 1%")
      (fields
        (field (name "PART NUMBER") "R0402_510R_1%_0.0625W_100PPM")
        (field (name "POWER") "0.0625W")
        (field (name "AUTHOR") "CERN DEM JLC")
      )
      (libsource (lib "Resistors") (part "Resistor - 1%"))
    )
    (comp (ref "R10")
      (value "510")
      (footprint "RESC1005X40N")
      (description "Resistor - 1%")
      (fields
        (field (name "PART NUMBER") "R0402_510R_1%_0.0625W_100PPM")
        (field (name "POWER") "0.0625W")
        (field (name "AUTHOR") "CERN DEM JLC")
      )
      (libsource (lib "Resistors") (part "Resistor - 1%"))
    )
    (comp (ref "R11")
      (value "510")
      (footprint "RESC1005X40N")
      (description "Resistor - 1%")
      (fields
        (field (name "PART NUMBER") "R0402_510R_1%_0.0625W_100PPM")
        (field (name "POWER") "0.0625W")
        (field (name "AUTHOR") "CERN DEM JLC")
      )
      (libsource (lib "Resistors") (part "Resistor - 1%"))
    )
    (comp (ref "R12")
      (value "Undefined")
      (footprint "RESC1005X40N")
      (description "Resistor")
      (fields (field (name "PART NUMBER") "R0402_NO-VALUE") (field (name "AUTHOR") "CERN DEM JLC"))
      (libsource (lib "Resistors") (part "Resistor"))
    )
    (comp (ref "R13")
      (value "30")
      (footprint "RESC2012X60N")
      (description "Resistor - 1%")
      (fields
        (field (name "PART NUMBER") "R0805_30R_1%_0.125W_100PPM")
        (field (name "POWER") "0.125W")
        (field (name "AUTHOR") "CERN DEM JLC")
      )
      (libsource (lib "Resistors") (part "Resistor - 1%"))
    )
    (comp (ref "R14")
      (value "30")
      (footprint "RESC2012X60N")
      (description "Resistor - 1%")
      (fields
        (field (name "PART NUMBER") "R0805_30R_1%_0.125W_100PPM")
        (field (name "POWER") "0.125W")
        (field (name "AUTHOR") "CERN DEM JLC")
      )
      (libsource (lib "Resistors") (part "Resistor - 1%"))
    )
    (comp (ref "R15")
      (value "30")
      (footprint "RESC2012X60N")
      (description "Resistor - 1%")
      (fields
        (field (name "PART NUMBER") "R0805_30R_1%_0.125W_100PPM")
        (field (name "POWER") "0.125W")
        (field (name "AUTHOR") "CERN DEM JLC")
      )
      (libsource (lib "Resistors") (part "Resistor - 1%"))
    )
    (comp (ref "R16")
      (value "30")
      (footprint "RESC2012X60N")
      (description "Resistor - 1%")
      (fields
        (field (name "PART NUMBER") "R0805_30R_1%_0.125W_100PPM")
        (field (name "POWER") "0.125W")
        (field (name "AUTHOR") "CERN DEM JLC")
      )
      (libsource (lib "Resistors") (part "Resistor - 1%"))
    )
    (comp (ref "R17")
      (value "100")
      (footprint "RESC1005X40N")
      (description "Resistor - 1%")
      (fields
        (field (name "PART NUMBER") "R0402_100R_1%_0.1W_100PPM")
        (field (name "POWER") "0.1W")
        (field (name "AUTHOR") "CERN DEM JLC")
      )
      (libsource (lib "Resistors") (part "Resistor - 1%"))
    )
    (comp (ref "R18")
      (value "100k")
      (footprint "RESC2012X60N")
      (description "Resistor - 1%")
      (fields
        (field (name "PART NUMBER") "R0805_100K_1%_0.125W_100PPM")
        (field (name "POWER") "0.125W")
        (field (name "AUTHOR") "CERN DEM JLC")
      )
      (libsource (lib "Resistors") (part "Resistor - 1%"))
    )
    (comp (ref "R19")
      (value "Undefined")
      (footprint "RESC1005X40N")
      (description "Resistor")
      (fields (field (name "PART NUMBER") "R0402_NO-VALUE") (field (name "AUTHOR") "CERN DEM JLC"))
      (libsource (lib "Resistors") (part "Resistor"))
    )
    (comp (ref "R20")
      (value "30")
      (footprint "RESC2012X60N")
      (description "Resistor - 1%")
      (fields
        (field (name "PART NUMBER") "R0805_30R_1%_0.125W_100PPM")
        (field (name "POWER") "0.125W")
        (field (name "AUTHOR") "CERN DEM JLC")
      )
      (libsource (lib "Resistors") (part "Resistor - 1%"))
    )
    (comp (ref "R21")
      (value "30")
      (footprint "RESC2012X60N")
      (description "Resistor - 1%")
      (fields
        (field (name "PART NUMBER") "R0805_30R_1%_0.125W_100PPM")
        (field (name "POWER") "0.125W")
        (field (name "AUTHOR") "CERN DEM JLC")
      )
      (libsource (lib "Resistors") (part "Resistor - 1%"))
    )
    (comp (ref "R22")
      (value "30")
      (footprint "RESC2012X60N")
      (description "Resistor - 1%")
      (fields
        (field (name "PART NUMBER") "R0805_30R_1%_0.125W_100PPM")
        (field (name "POWER") "0.125W")
        (field (name "AUTHOR") "CERN DEM JLC")
      )
      (libsource (lib "Resistors") (part "Resistor - 1%"))
    )
    (comp (ref "R23")
      (value "30")
      (footprint "RESC2012X60N")
      (description "Resistor - 1%")
      (fields
        (field (name "PART NUMBER") "R0805_30R_1%_0.125W_100PPM")
        (field (name "POWER") "0.125W")
        (field (name "AUTHOR") "CERN DEM JLC")
      )
      (libsource (lib "Resistors") (part "Resistor - 1%"))
    )
    (comp (ref "R24")
      (value "100")
      (footprint "RESC1005X40N")
      (description "Resistor - 1%")
      (fields
        (field (name "PART NUMBER") "R0402_100R_1%_0.1W_100PPM")
        (field (name "POWER") "0.1W")
        (field (name "AUTHOR") "CERN DEM JLC")
      )
      (libsource (lib "Resistors") (part "Resistor - 1%"))
    )
    (comp (ref "R25")
      (value "100k")
      (footprint "RESC2012X60N")
      (description "Resistor - 1%")
      (fields
        (field (name "PART NUMBER") "R0805_100K_1%_0.125W_100PPM")
        (field (name "POWER") "0.125W")
        (field (name "AUTHOR") "CERN DEM JLC")
      )
      (libsource (lib "Resistors") (part "Resistor - 1%"))
    )
    (comp (ref "R134")
      (value "220")
      (footprint "RESC1608X55N")
      (description "Resistor - 1%")
      (fields
        (field (name "PART NUMBER") "R0603_220R_1%_0.1W_100PPM")
        (field (name "POWER") "0.1W")
        (field (name "AUTHOR") "CERN DEM JLC")
      )
      (libsource (lib "Resistors") (part "Resistor - 1%"))
    )
    (comp (ref "R135")
      (value "220")
      (footprint "RESC1608X55N")
      (description "Resistor - 1%")
      (fields
        (field (name "PART NUMBER") "R0603_220R_1%_0.1W_100PPM")
        (field (name "POWER") "0.1W")
        (field (name "AUTHOR") "CERN DEM JLC")
      )
      (libsource (lib "Resistors") (part "Resistor - 1%"))
    )
    (comp (ref "R136")
      (value "10k")
      (footprint "RESC1005X40N")
      (description "Resistor - 1%")
      (fields
        (field (name "PART NUMBER") "R0402_10K_1%_0.0625W_100PPM")
        (field (name "POWER") "0.0625W")
        (field (name "AUTHOR") "CERN DEM JLC")
      )
      (libsource (lib "Resistors") (part "Resistor - 1%"))
    )
    (comp (ref "R137")
      (value "10k")
      (footprint "RESC1005X40N")
      (description "Resistor - 1%")
      (fields
        (field (name "PART NUMBER") "R0402_10K_1%_0.0625W_100PPM")
        (field (name "POWER") "0.0625W")
        (field (name "AUTHOR") "CERN DEM JLC")
      )
      (libsource (lib "Resistors") (part "Resistor - 1%"))
    )
    (comp (ref "R138")
      (value "100")
      (footprint "RESC1005X40N")
      (description "Resistor - 1%")
      (fields
        (field (name "PART NUMBER") "R0402_100R_1%_0.1W_100PPM")
        (field (name "POWER") "0.1W")
        (field (name "AUTHOR") "CERN DEM JLC")
      )
      (libsource (lib "Resistors") (part "Resistor - 1%"))
    )
    (comp (ref "R139")
      (value "49R9")
      (footprint "RESC3225X70N")
      (description "Resistor - 1%")
      (fields
        (field (name "PART NUMBER") "R1210_49R9_1%_0.5W_100PPM_VISHAY_CRCW")
        (field (name "POWER") "0.5W")
        (field (name "AUTHOR") "CERN DEM JMW")
      )
      (libsource (lib "Resistors") (part "Resistor - 1%"))
    )
    (comp (ref "R140")
      (value "10k")
      (footprint "RESC1005X40N")
      (description "Resistor - 1%")
      (fields
        (field (name "PART NUMBER") "R0402_10K_1%_0.0625W_100PPM")
        (field (name "POWER") "0.0625W")
        (field (name "AUTHOR") "CERN DEM JLC")
      )
      (libsource (lib "Resistors") (part "Resistor - 1%"))
    )
    (comp (ref "R141")
      (value "100")
      (footprint "RESC1005X40N")
      (description "Resistor - 1%")
      (fields
        (field (name "PART NUMBER") "R0402_100R_1%_0.1W_100PPM")
        (field (name "POWER") "0.1W")
        (field (name "AUTHOR") "CERN DEM JLC")
      )
      (libsource (lib "Resistors") (part "Resistor - 1%"))
    )
    (comp (ref "R142")
      (value "49R9")
      (footprint "RESC3225X70N")
      (description "Resistor - 1%")
      (fields
        (field (name "PART NUMBER") "R1210_49R9_1%_0.5W_100PPM_VISHAY_CRCW")
        (field (name "POWER") "0.5W")
        (field (name "AUTHOR") "CERN DEM JMW")
      )
      (libsource (lib "Resistors") (part "Resistor - 1%"))
    )
    (comp (ref "R143")
      (value "10k")
      (footprint "RESC1005X40N")
      (description "Resistor - 1%")
      (fields
        (field (name "PART NUMBER") "R0402_10K_1%_0.0625W_100PPM")
        (field (name "POWER") "0.0625W")
        (field (name "AUTHOR") "CERN DEM JLC")
      )
      (libsource (lib "Resistors") (part "Resistor - 1%"))
    )
    (comp (ref "R144")
      (value "100")
      (footprint "RESC1005X40N")
      (description "Resistor - 1%")
      (fields
        (field (name "PART NUMBER") "R0402_100R_1%_0.1W_100PPM")
        (field (name "POWER") "0.1W")
        (field (name "AUTHOR") "CERN DEM JLC")
      )
      (libsource (lib "Resistors") (part "Resistor - 1%"))
    )
    (comp (ref "R145")
      (value "49R9")
      (footprint "RESC3225X70N")
      (description "Resistor - 1%")
      (fields
        (field (name "PART NUMBER") "R1210_49R9_1%_0.5W_100PPM_VISHAY_CRCW")
        (field (name "POWER") "0.5W")
        (field (name "AUTHOR") "CERN DEM JMW")
      )
      (libsource (lib "Resistors") (part "Resistor - 1%"))
    )
    (comp (ref "R146")
      (value "10k")
      (footprint "RESC1005X40N")
      (description "Resistor - 1%")
      (fields
        (field (name "PART NUMBER") "R0402_10K_1%_0.0625W_100PPM")
        (field (name "POWER") "0.0625W")
        (field (name "AUTHOR") "CERN DEM JLC")
      )
      (libsource (lib "Resistors") (part "Resistor - 1%"))
    )
    (comp (ref "R147")
      (value "100")
      (footprint "RESC1005X40N")
      (description "Resistor - 1%")
      (fields
        (field (name "PART NUMBER") "R0402_100R_1%_0.1W_100PPM")
        (field (name "POWER") "0.1W")
        (field (name "AUTHOR") "CERN DEM JLC")
      )
      (libsource (lib "Resistors") (part "Resistor - 1%"))
    )
    (comp (ref "R148")
      (value "49R9")
      (footprint "RESC3225X70N")
      (description "Resistor - 1%")
      (fields
        (field (name "PART NUMBER") "R1210_49R9_1%_0.5W_100PPM_VISHAY_CRCW")
        (field (name "POWER") "0.5W")
        (field (name "AUTHOR") "CERN DEM JMW")
      )
      (libsource (lib "Resistors") (part "Resistor - 1%"))
    )
    (comp (ref "R149")
      (value "10k")
      (footprint "RESC1005X40N")
      (description "Resistor - 1%")
      (fields
        (field (name "PART NUMBER") "R0402_10K_1%_0.0625W_100PPM")
        (field (name "POWER") "0.0625W")
        (field (name "AUTHOR") "CERN DEM JLC")
      )
      (libsource (lib "Resistors") (part "Resistor - 1%"))
    )
    (comp (ref "R150")
      (value "10k")
      (footprint "RESC1005X40N")
      (description "Resistor - 1%")
      (fields
        (field (name "PART NUMBER") "R0402_10K_1%_0.0625W_100PPM")
        (field (name "POWER") "0.0625W")
        (field (name "AUTHOR") "CERN DEM JLC")
      )
      (libsource (lib "Resistors") (part "Resistor - 1%"))
    )
    (comp (ref "R151")
      (value "100")
      (footprint "RESC1005X40N")
      (description "Resistor - 1%")
      (fields
        (field (name "PART NUMBER") "R0402_100R_1%_0.1W_100PPM")
        (field (name "POWER") "0.1W")
        (field (name "AUTHOR") "CERN DEM JLC")
      )
      (libsource (lib "Resistors") (part "Resistor - 1%"))
    )
    (comp (ref "R152")
      (value "10k")
      (footprint "RESC1005X40N")
      (description "Resistor - 1%")
      (fields
        (field (name "PART NUMBER") "R0402_10K_1%_0.0625W_100PPM")
        (field (name "POWER") "0.0625W")
        (field (name "AUTHOR") "CERN DEM JLC")
      )
      (libsource (lib "Resistors") (part "Resistor - 1%"))
    )
    (comp (ref "R153")
      (value "220")
      (footprint "RESC1608X55N")
      (description "Resistor - 1%")
      (fields
        (field (name "PART NUMBER") "R0603_220R_1%_0.1W_100PPM")
        (field (name "POWER") "0.1W")
        (field (name "AUTHOR") "CERN DEM JLC")
      )
      (libsource (lib "Resistors") (part "Resistor - 1%"))
    )
    (comp (ref "R154")
      (value "220")
      (footprint "RESC1608X55N")
      (description "Resistor - 1%")
      (fields
        (field (name "PART NUMBER") "R0603_220R_1%_0.1W_100PPM")
        (field (name "POWER") "0.1W")
        (field (name "AUTHOR") "CERN DEM JLC")
      )
      (libsource (lib "Resistors") (part "Resistor - 1%"))
    )
    (comp (ref "R155")
      (value "10k")
      (footprint "RESC1005X40N")
      (description "Resistor - 1%")
      (fields
        (field (name "PART NUMBER") "R0402_10K_1%_0.0625W_100PPM")
        (field (name "POWER") "0.0625W")
        (field (name "AUTHOR") "CERN DEM JLC")
      )
      (libsource (lib "Resistors") (part "Resistor - 1%"))
    )
    (comp (ref "R156")
      (value "10k")
      (footprint "RESC1005X40N")
      (description "Resistor - 1%")
      (fields
        (field (name "PART NUMBER") "R0402_10K_1%_0.0625W_100PPM")
        (field (name "POWER") "0.0625W")
        (field (name "AUTHOR") "CERN DEM JLC")
      )
      (libsource (lib "Resistors") (part "Resistor - 1%"))
    )
    (comp (ref "R157")
      (value "100")
      (footprint "RESC1005X40N")
      (description "Resistor - 1%")
      (fields
        (field (name "PART NUMBER") "R0402_100R_1%_0.1W_100PPM")
        (field (name "POWER") "0.1W")
        (field (name "AUTHOR") "CERN DEM JLC")
      )
      (libsource (lib "Resistors") (part "Resistor - 1%"))
    )
    (comp (ref "R158")
      (value "49R9")
      (footprint "RESC3225X70N")
      (description "Resistor - 1%")
      (fields
        (field (name "PART NUMBER") "R1210_49R9_1%_0.5W_100PPM_VISHAY_CRCW")
        (field (name "POWER") "0.5W")
        (field (name "AUTHOR") "CERN DEM JMW")
      )
      (libsource (lib "Resistors") (part "Resistor - 1%"))
    )
    (comp (ref "R159")
      (value "10k")
      (footprint "RESC1005X40N")
      (description "Resistor - 1%")
      (fields
        (field (name "PART NUMBER") "R0402_10K_1%_0.0625W_100PPM")
        (field (name "POWER") "0.0625W")
        (field (name "AUTHOR") "CERN DEM JLC")
      )
      (libsource (lib "Resistors") (part "Resistor - 1%"))
    )
    (comp (ref "R160")
      (value "100")
      (footprint "RESC1005X40N")
      (description "Resistor - 1%")
      (fields
        (field (name "PART NUMBER") "R0402_100R_1%_0.1W_100PPM")
        (field (name "POWER") "0.1W")
        (field (name "AUTHOR") "CERN DEM JLC")
      )
      (libsource (lib "Resistors") (part "Resistor - 1%"))
    )
    (comp (ref "R161")
      (value "49R9")
      (footprint "RESC3225X70N")
      (description "Resistor - 1%")
      (fields
        (field (name "PART NUMBER") "R1210_49R9_1%_0.5W_100PPM_VISHAY_CRCW")
        (field (name "POWER") "0.5W")
        (field (name "AUTHOR") "CERN DEM JMW")
      )
      (libsource (lib "Resistors") (part "Resistor - 1%"))
    )
    (comp (ref "R162")
      (value "10k")
      (footprint "RESC1005X40N")
      (description "Resistor - 1%")
      (fields
        (field (name "PART NUMBER") "R0402_10K_1%_0.0625W_100PPM")
        (field (name "POWER") "0.0625W")
        (field (name "AUTHOR") "CERN DEM JLC")
      )
      (libsource (lib "Resistors") (part "Resistor - 1%"))
    )
    (comp (ref "R163")
      (value "100")
      (footprint "RESC1005X40N")
      (description "Resistor - 1%")
      (fields
        (field (name "PART NUMBER") "R0402_100R_1%_0.1W_100PPM")
        (field (name "POWER") "0.1W")
        (field (name "AUTHOR") "CERN DEM JLC")
      )
      (libsource (lib "Resistors") (part "Resistor - 1%"))
    )
    (comp (ref "R164")
      (value "49R9")
      (footprint "RESC3225X70N")
      (description "Resistor - 1%")
      (fields
        (field (name "PART NUMBER") "R1210_49R9_1%_0.5W_100PPM_VISHAY_CRCW")
        (field (name "POWER") "0.5W")
        (field (name "AUTHOR") "CERN DEM JMW")
      )
      (libsource (lib "Resistors") (part "Resistor - 1%"))
    )
    (comp (ref "R165")
      (value "10k")
      (footprint "RESC1005X40N")
      (description "Resistor - 1%")
      (fields
        (field (name "PART NUMBER") "R0402_10K_1%_0.0625W_100PPM")
        (field (name "POWER") "0.0625W")
        (field (name "AUTHOR") "CERN DEM JLC")
      )
      (libsource (lib "Resistors") (part "Resistor - 1%"))
    )
    (comp (ref "R166")
      (value "100")
      (footprint "RESC1005X40N")
      (description "Resistor - 1%")
      (fields
        (field (name "PART NUMBER") "R0402_100R_1%_0.1W_100PPM")
        (field (name "POWER") "0.1W")
        (field (name "AUTHOR") "CERN DEM JLC")
      )
      (libsource (lib "Resistors") (part "Resistor - 1%"))
    )
    (comp (ref "R167")
      (value "270k")
      (footprint "RESC1608X55N")
      (description "Resistor - 1%")
      (fields
        (field (name "PART NUMBER") "R0603_270K_1%_0.1W_100PPM")
        (field (name "POWER") "0.1W")
        (field (name "AUTHOR") "CERN DEM JLC")
      )
      (libsource (lib "Resistors") (part "Resistor - 1%"))
    )
    (comp (ref "R168")
      (value "49R9")
      (footprint "RESC3225X70N")
      (description "Resistor - 1%")
      (fields
        (field (name "PART NUMBER") "R1210_49R9_1%_0.5W_100PPM_VISHAY_CRCW")
        (field (name "POWER") "0.5W")
        (field (name "AUTHOR") "CERN DEM JMW")
      )
      (libsource (lib "Resistors") (part "Resistor - 1%"))
    )
    (comp (ref "R169")
      (value "10k")
      (footprint "RESC1005X40N")
      (description "Resistor - 1%")
      (fields
        (field (name "PART NUMBER") "R0402_10K_1%_0.0625W_100PPM")
        (field (name "POWER") "0.0625W")
        (field (name "AUTHOR") "CERN DEM JLC")
      )
      (libsource (lib "Resistors") (part "Resistor - 1%"))
    )
    (comp (ref "R170")
      (value "100")
      (footprint "RESC1005X40N")
      (description "Resistor - 1%")
      (fields
        (field (name "PART NUMBER") "R0402_100R_1%_0.1W_100PPM")
        (field (name "POWER") "0.1W")
        (field (name "AUTHOR") "CERN DEM JLC")
      )
      (libsource (lib "Resistors") (part "Resistor - 1%"))
    )
    (comp (ref "R171")
      (value "10k")
      (footprint "RESC1005X40N")
      (description "Resistor - 1%")
      (fields
        (field (name "PART NUMBER") "R0402_10K_1%_0.0625W_100PPM")
        (field (name "POWER") "0.0625W")
        (field (name "AUTHOR") "CERN DEM JLC")
      )
      (libsource (lib "Resistors") (part "Resistor - 1%"))
    )
    (comp (ref "R172")
      (value "10k")
      (footprint "RESC1005X40N")
      (description "Resistor - 1%")
      (fields
        (field (name "PART NUMBER") "R0402_10K_1%_0.0625W_100PPM")
        (field (name "POWER") "0.0625W")
        (field (name "AUTHOR") "CERN DEM JLC")
      )
      (libsource (lib "Resistors") (part "Resistor - 1%"))
    )
    (comp (ref "R173")
      (value "82k")
      (footprint "RESC1608X55N")
      (description "Resistor - 1%")
      (fields
        (field (name "PART NUMBER") "R0603_82K_1%_0.1W_100PPM")
        (field (name "POWER") "0.1W")
        (field (name "AUTHOR") "CERN DEM JLC")
      )
      (libsource (lib "Resistors") (part "Resistor - 1%"))
    )
    (comp (ref "SW1")
      (value "Switch")
      (footprint "SW_OMRON_A6S-4102-H")
      (description "4 Ways SPST DIP Switch")
      (fields
        (field (name "PART NUMBER") "SW_OMRON_A6S-4102-H")
        (field (name "MANUFACTURER") "OMRON")
        (field (name "AUTHOR") "CERN DEM JMW")
      )
      (libsource (lib "Eletro-mechanical") (part "SW 4x SPST DIP Switch"))
    )
    (comp (ref "SW2")
      (value "Switch")
      (footprint "SW_OMRON_A6S-4102-H")
      (description "4 Ways SPST DIP Switch")
      (fields
        (field (name "PART NUMBER") "SW_OMRON_A6S-4102-H")
        (field (name "MANUFACTURER") "OMRON")
        (field (name "AUTHOR") "CERN DEM JMW")
      )
      (libsource (lib "Eletro-mechanical") (part "SW 4x SPST DIP Switch"))
    )
    (comp (ref "SW9")
      (value "Switch")
      (footprint "SW_OMRON_A6S-2102-H")
      (description "2 Ways SPST DIP Switch")
      (fields
        (field (name "PART NUMBER") "SW_OMRON_A6S-2102-H")
        (field (name "MANUFACTURER") "OMRON")
        (field (name "AUTHOR") "CERN DEM JMW")
      )
      (libsource (lib "Eletro-mechanical") (part "SW 2x SPST DIP Switch"))
    )
    (comp (ref "T1")
      (value "BSS138LT1G")
      (footprint "SOT95P240X110-3N")
      (description "N-CHANNEL MOSFET WITH DIODE")
      (fields (field (name "MANUFACTURER") "ON SEMICONDUCTOR") (field (name "AUTHOR") "CERN DEM JLC"))
      (libsource (lib "ICs And Semiconductors") (part "N-MOSFET-D 1G 2S 3D"))
    )
    (comp (ref "T2")
      (value "BSS138LT1G")
      (footprint "SOT95P240X110-3N")
      (description "N-CHANNEL MOSFET WITH DIODE")
      (fields (field (name "MANUFACTURER") "ON SEMICONDUCTOR") (field (name "AUTHOR") "CERN DEM JLC"))
      (libsource (lib "ICs And Semiconductors") (part "N-MOSFET-D 1G 2S 3D"))
    )
    (comp (ref "T3")
      (value "BSS138LT1G")
      (footprint "SOT95P240X110-3N")
      (description "N-CHANNEL MOSFET WITH DIODE")
      (fields (field (name "MANUFACTURER") "ON SEMICONDUCTOR") (field (name "AUTHOR") "CERN DEM JLC"))
      (libsource (lib "ICs And Semiconductors") (part "N-MOSFET-D 1G 2S 3D"))
    )
    (comp (ref "T4")
      (value "BSS138LT1G")
      (footprint "SOT95P240X110-3N")
      (description "N-CHANNEL MOSFET WITH DIODE")
      (fields (field (name "MANUFACTURER") "ON SEMICONDUCTOR") (field (name "AUTHOR") "CERN DEM JLC"))
      (libsource (lib "ICs And Semiconductors") (part "N-MOSFET-D 1G 2S 3D"))
    )
    (comp (ref "T5")
      (value "BSS138LT1G")
      (footprint "SOT95P240X110-3N")
      (description "N-CHANNEL MOSFET WITH DIODE")
      (fields (field (name "MANUFACTURER") "ON SEMICONDUCTOR") (field (name "AUTHOR") "CERN DEM JLC"))
      (libsource (lib "ICs And Semiconductors") (part "N-MOSFET-D 1G 2S 3D"))
    )
    (comp (ref "T6")
      (value "BSS138LT1G")
      (footprint "SOT95P240X110-3N")
      (description "N-CHANNEL MOSFET WITH DIODE")
      (fields (field (name "MANUFACTURER") "ON SEMICONDUCTOR") (field (name "AUTHOR") "CERN DEM JLC"))
      (libsource (lib "ICs And Semiconductors") (part "N-MOSFET-D 1G 2S 3D"))
    )
    (comp (ref "T7")
      (value "BSS138LT1G")
      (footprint "SOT95P240X110-3N")
      (description "N-CHANNEL MOSFET WITH DIODE")
      (fields (field (name "MANUFACTURER") "ON SEMICONDUCTOR") (field (name "AUTHOR") "CERN DEM JLC"))
      (libsource (lib "ICs And Semiconductors") (part "N-MOSFET-D 1G 2S 3D"))
    )
    (comp (ref "T8")
      (value "BSS138LT1G")
      (footprint "SOT95P240X110-3N")
      (description "N-CHANNEL MOSFET WITH DIODE")
      (fields (field (name "MANUFACTURER") "ON SEMICONDUCTOR") (field (name "AUTHOR") "CERN DEM JLC"))
      (libsource (lib "ICs And Semiconductors") (part "N-MOSFET-D 1G 2S 3D"))
    )
    (comp (ref "T26")
      (value "BSS138LT1G")
      (footprint "SOT95P240X110-3N")
      (description "N-CHANNEL MOSFET WITH DIODE")
      (fields (field (name "MANUFACTURER") "ON SEMICONDUCTOR") (field (name "AUTHOR") "CERN DEM JLC"))
      (libsource (lib "ICs And Semiconductors") (part "N-MOSFET-D 1G 2S 3D"))
    )
    (comp (ref "T27")
      (value "BSS138LT1G")
      (footprint "SOT95P240X110-3N")
      (description "N-CHANNEL MOSFET WITH DIODE")
      (fields (field (name "MANUFACTURER") "ON SEMICONDUCTOR") (field (name "AUTHOR") "CERN DEM JLC"))
      (libsource (lib "ICs And Semiconductors") (part "N-MOSFET-D 1G 2S 3D"))
    )
    (comp (ref "T28")
      (value "BSS138LT1G")
      (footprint "SOT95P240X110-3N")
      (description "N-CHANNEL MOSFET WITH DIODE")
      (fields (field (name "MANUFACTURER") "ON SEMICONDUCTOR") (field (name "AUTHOR") "CERN DEM JLC"))
      (libsource (lib "ICs And Semiconductors") (part "N-MOSFET-D 1G 2S 3D"))
    )
    (comp (ref "T29")
      (value "BSS138LT1G")
      (footprint "SOT95P240X110-3N")
      (description "N-CHANNEL MOSFET WITH DIODE")
      (fields (field (name "MANUFACTURER") "ON SEMICONDUCTOR") (field (name "AUTHOR") "CERN DEM JLC"))
      (libsource (lib "ICs And Semiconductors") (part "N-MOSFET-D 1G 2S 3D"))
    )
  )
  (nets
    (net (code "1") (name "/DIR_CTRL0") (class "Default")
      (node (ref "IC13") (pin "4") (pinfunction "P0_4") (pintype "bidirectional"))
      (node (ref "IC13") (pin "5") (pinfunction "P1_5") (pintype "bidirectional"))
      (node (ref "IC13") (pin "6") (pinfunction "P2_6") (pintype "bidirectional"))
      (node (ref "IC13") (pin "7") (pinfunction "P3_7") (pintype "bidirectional"))
      (node (ref "IC21") (pin "1") (pinfunction "1DE_1") (pintype "input"))
      (node (ref "IC21") (pin "12") (pinfunction "4DE_12") (pintype "input"))
      (node (ref "IC21") (pin "19") (pinfunction "~{3RE}_19") (pintype "input"))
      (node (ref "IC21") (pin "21") (pinfunction "~{4RE}_21") (pintype "input"))
      (node (ref "IC21") (pin "40") (pinfunction "~{1RE}_40") (pintype "input"))
      (node (ref "IC21") (pin "42") (pinfunction "~{2RE}_42") (pintype "input"))
      (node (ref "IC21") (pin "5") (pinfunction "2DE_5") (pintype "input"))
      (node (ref "IC21") (pin "8") (pinfunction "3DE_8") (pintype "input"))
      (node (ref "R134") (pin "2") (pinfunction "2_2") (pintype "passive"))
      (node (ref "R137") (pin "1") (pinfunction "1_1") (pintype "passive"))
      (node (ref "SW9") (pin "1") (pinfunction "1_1") (pintype "passive"))
      (node (ref "T26") (pin "1") (pinfunction "G_1") (pintype "passive"))
    )
    (net (code "2") (name "/DIR_CTRL1") (class "Default")
      (node (ref "IC13") (pin "10") (pinfunction "P5_10") (pintype "bidirectional"))
      (node (ref "IC13") (pin "11") (pinfunction "P6_11") (pintype "bidirectional"))
      (node (ref "IC13") (pin "12") (pinfunction "P7_12") (pintype "bidirectional"))
      (node (ref "IC13") (pin "9") (pinfunction "P4_9") (pintype "bidirectional"))
      (node (ref "IC9") (pin "1") (pinfunction "1DE_1") (pintype "input"))
      (node (ref "IC9") (pin "12") (pinfunction "4DE_12") (pintype "input"))
      (node (ref "IC9") (pin "19") (pinfunction "~{3RE}_19") (pintype "input"))
      (node (ref "IC9") (pin "21") (pinfunction "~{4RE}_21") (pintype "input"))
      (node (ref "IC9") (pin "40") (pinfunction "~{1RE}_40") (pintype "input"))
      (node (ref "IC9") (pin "42") (pinfunction "~{2RE}_42") (pintype "input"))
      (node (ref "IC9") (pin "5") (pinfunction "2DE_5") (pintype "input"))
      (node (ref "IC9") (pin "8") (pinfunction "3DE_8") (pintype "input"))
      (node (ref "R153") (pin "2") (pinfunction "2_2") (pintype "passive"))
      (node (ref "R156") (pin "1") (pinfunction "1_1") (pintype "passive"))
      (node (ref "SW9") (pin "2") (pinfunction "2_2") (pintype "passive"))
      (node (ref "T28") (pin "1") (pinfunction "G_1") (pintype "passive"))
    )
    (net (code "3") (name "/I2C_SCL") (class "Default")
      (node (ref "B8") (pin "1") (pinfunction "1_1") (pintype "bidirectional"))
      (node (ref "IC13") (pin "14") (pinfunction "SCL_14") (pintype "input"))
      (node (ref "IC32") (pin "1") (pinfunction "SCL_1") (pintype "input"))
      (node (ref "J37") (pin "27") (pinfunction "27_27") (pintype "bidirectional"))
    )
    (net (code "4") (name "/I2C_SDA") (class "Default")
      (node (ref "B7") (pin "1") (pinfunction "1_1") (pintype "bidirectional"))
      (node (ref "IC13") (pin "15") (pinfunction "SDA_15") (pintype "bidirectional"))
      (node (ref "IC32") (pin "3") (pinfunction "SDA_3") (pintype "bidirectional"))
      (node (ref "J37") (pin "26") (pinfunction "26_26") (pintype "bidirectional"))
    )
    (net (code "5") (name "/IO0") (class "Default")
      (node (ref "J1") (pin "4") (pinfunction "4_4") (pintype "bidirectional"))
      (node (ref "R13") (pin "1") (pinfunction "1_1") (pintype "passive"))
      (node (ref "R139") (pin "2") (pinfunction "2_2") (pintype "passive"))
    )
    (net (code "6") (name "/IO1") (class "Default")
      (node (ref "J1") (pin "2") (pinfunction "2_2") (pintype "bidirectional"))
      (node (ref "R14") (pin "1") (pinfunction "1_1") (pintype "passive"))
      (node (ref "R142") (pin "2") (pinfunction "2_2") (pintype "passive"))
    )
    (net (code "7") (name "/IO2") (class "Default")
      (node (ref "J2") (pin "4") (pinfunction "4_4") (pintype "bidirectional"))
      (node (ref "R145") (pin "2") (pinfunction "2_2") (pintype "passive"))
      (node (ref "R15") (pin "1") (pinfunction "1_1") (pintype "passive"))
    )
    (net (code "8") (name "/IO3") (class "Default")
      (node (ref "J2") (pin "2") (pinfunction "2_2") (pintype "bidirectional"))
      (node (ref "R148") (pin "2") (pinfunction "2_2") (pintype "passive"))
      (node (ref "R16") (pin "1") (pinfunction "1_1") (pintype "passive"))
    )
    (net (code "9") (name "/IO4") (class "Default")
      (node (ref "J3") (pin "4") (pinfunction "4_4") (pintype "bidirectional"))
      (node (ref "R158") (pin "2") (pinfunction "2_2") (pintype "passive"))
      (node (ref "R20") (pin "1") (pinfunction "1_1") (pintype "passive"))
    )
    (net (code "10") (name "/IO5") (class "Default")
      (node (ref "J3") (pin "2") (pinfunction "2_2") (pintype "bidirectional"))
      (node (ref "R161") (pin "2") (pinfunction "2_2") (pintype "passive"))
      (node (ref "R21") (pin "1") (pinfunction "1_1") (pintype "passive"))
    )
    (net (code "11") (name "/IO6") (class "Default")
      (node (ref "J4") (pin "4") (pinfunction "4_4") (pintype "bidirectional"))
      (node (ref "R164") (pin "2") (pinfunction "2_2") (pintype "passive"))
      (node (ref "R22") (pin "1") (pinfunction "1_1") (pintype "passive"))
    )
    (net (code "12") (name "/IO7") (class "Default")
      (node (ref "J4") (pin "2") (pinfunction "2_2") (pintype "bidirectional"))
      (node (ref "R168") (pin "2") (pinfunction "2_2") (pintype "passive"))
      (node (ref "R23") (pin "1") (pinfunction "1_1") (pintype "passive"))
    )
    (net (code "13") (name "/LED0") (class "Default")
      (node (ref "LD2") (pin "2") (pinfunction "A_2") (pintype "passive"))
      (node (ref "R1") (pin "2") (pinfunction "2_2") (pintype "passive"))
    )
    (net (code "14") (name "/LED1") (class "Default")
      (node (ref "LD2") (pin "4") (pinfunction "A_4") (pintype "passive"))
      (node (ref "R2") (pin "2") (pinfunction "2_2") (pintype "passive"))
    )
    (net (code "15") (name "/LED2") (class "Default")
      (node (ref "LD1") (pin "4") (pinfunction "A_4") (pintype "passive"))
      (node (ref "R3") (pin "2") (pinfunction "2_2") (pintype "passive"))
    )
    (net (code "16") (name "/LED3") (class "Default")
      (node (ref "LD1") (pin "2") (pinfunction "A_2") (pintype "passive"))
      (node (ref "R4") (pin "2") (pinfunction "2_2") (pintype "passive"))
    )
    (net (code "17") (name "/LED4") (class "Default")
      (node (ref "LD8") (pin "4") (pinfunction "A_4") (pintype "passive"))
      (node (ref "R5") (pin "2") (pinfunction "2_2") (pintype "passive"))
    )
    (net (code "18") (name "/LED5") (class "Default")
      (node (ref "LD8") (pin "2") (pinfunction "A_2") (pintype "passive"))
      (node (ref "R7") (pin "2") (pinfunction "2_2") (pintype "passive"))
    )
    (net (code "19") (name "/LED6") (class "Default")
      (node (ref "LD3") (pin "4") (pinfunction "A_4") (pintype "passive"))
      (node (ref "R9") (pin "2") (pinfunction "2_2") (pintype "passive"))
    )
    (net (code "20") (name "/LED7") (class "Default")
      (node (ref "LD3") (pin "2") (pinfunction "A_2") (pintype "passive"))
      (node (ref "R11") (pin "2") (pinfunction "2_2") (pintype "passive"))
    )
    (net (code "21") (name "/LVDS0_N") (class "Default")
      (node (ref "IC21") (pin "48") (pinfunction "1B_48") (pintype "bidirectional"))
      (node (ref "J37") (pin "3") (pinfunction "3_3") (pintype "bidirectional"))
      (node (ref "R141") (pin "2") (pinfunction "2_2") (pintype "passive"))
    )
    (net (code "22") (name "/LVDS0_P") (class "Default")
      (node (ref "IC21") (pin "47") (pinfunction "1A_47") (pintype "bidirectional"))
      (node (ref "J37") (pin "2") (pinfunction "2_2") (pintype "bidirectional"))
      (node (ref "R141") (pin "1") (pinfunction "1_1") (pintype "passive"))
    )
    (net (code "23") (name "/LVDS1_N") (class "Default")
      (node (ref "IC21") (pin "4") (pinfunction "2B_4") (pintype "bidirectional"))
      (node (ref "J37") (pin "6") (pinfunction "6_6") (pintype "bidirectional"))
      (node (ref "R144") (pin "2") (pinfunction "2_2") (pintype "passive"))
    )
    (net (code "24") (name "/LVDS1_P") (class "Default")
      (node (ref "IC21") (pin "3") (pinfunction "2A_3") (pintype "bidirectional"))
      (node (ref "J37") (pin "5") (pinfunction "5_5") (pintype "bidirectional"))
      (node (ref "R144") (pin "1") (pinfunction "1_1") (pintype "passive"))
    )
    (net (code "25") (name "/LVDS2_N") (class "Default")
      (node (ref "IC21") (pin "10") (pinfunction "3B_10") (pintype "bidirectional"))
      (node (ref "J37") (pin "9") (pinfunction "9_9") (pintype "bidirectional"))
      (node (ref "R147") (pin "2") (pinfunction "2_2") (pintype "passive"))
    )
    (net (code "26") (name "/LVDS2_P") (class "Default")
      (node (ref "IC21") (pin "9") (pinfunction "3A_9") (pintype "bidirectional"))
      (node (ref "J37") (pin "8") (pinfunction "8_8") (pintype "bidirectional"))
      (node (ref "R147") (pin "1") (pinfunction "1_1") (pintype "passive"))
    )
    (net (code "27") (name "/LVDS3_N") (class "Default")
      (node (ref "IC21") (pin "14") (pinfunction "4B_14") (pintype "bidirectional"))
      (node (ref "J37") (pin "12") (pinfunction "12_12") (pintype "bidirectional"))
      (node (ref "R151") (pin "2") (pinfunction "2_2") (pintype "passive"))
    )
    (net (code "28") (name "/LVDS3_P") (class "Default")
      (node (ref "IC21") (pin "13") (pinfunction "4A_13") (pintype "bidirectional"))
      (node (ref "J37") (pin "11") (pinfunction "11_11") (pintype "bidirectional"))
      (node (ref "R151") (pin "1") (pinfunction "1_1") (pintype "passive"))
    )
    (net (code "29") (name "/LVDS4_N") (class "Default")
      (node (ref "IC9") (pin "48") (pinfunction "1B_48") (pintype "bidirectional"))
      (node (ref "J37") (pin "15") (pinfunction "15_15") (pintype "bidirectional"))
      (node (ref "R160") (pin "2") (pinfunction "2_2") (pintype "passive"))
    )
    (net (code "30") (name "/LVDS4_P") (class "Default")
      (node (ref "IC9") (pin "47") (pinfunction "1A_47") (pintype "bidirectional"))
      (node (ref "J37") (pin "14") (pinfunction "14_14") (pintype "bidirectional"))
      (node (ref "R160") (pin "1") (pinfunction "1_1") (pintype "passive"))
    )
    (net (code "31") (name "/LVDS5_N") (class "Default")
      (node (ref "IC9") (pin "4") (pinfunction "2B_4") (pintype "bidirectional"))
      (node (ref "J37") (pin "18") (pinfunction "18_18") (pintype "bidirectional"))
      (node (ref "R163") (pin "2") (pinfunction "2_2") (pintype "passive"))
    )
    (net (code "32") (name "/LVDS5_P") (class "Default")
      (node (ref "IC9") (pin "3") (pinfunction "2A_3") (pintype "bidirectional"))
      (node (ref "J37") (pin "17") (pinfunction "17_17") (pintype "bidirectional"))
      (node (ref "R163") (pin "1") (pinfunction "1_1") (pintype "passive"))
    )
    (net (code "33") (name "/LVDS6_N") (class "Default")
      (node (ref "IC9") (pin "10") (pinfunction "3B_10") (pintype "bidirectional"))
      (node (ref "J37") (pin "21") (pinfunction "21_21") (pintype "bidirectional"))
      (node (ref "R166") (pin "2") (pinfunction "2_2") (pintype "passive"))
    )
    (net (code "34") (name "/LVDS6_P") (class "Default")
      (node (ref "IC9") (pin "9") (pinfunction "3A_9") (pintype "bidirectional"))
      (node (ref "J37") (pin "20") (pinfunction "20_20") (pintype "bidirectional"))
      (node (ref "R166") (pin "1") (pinfunction "1_1") (pintype "passive"))
    )
    (net (code "35") (name "/LVDS7_N") (class "Default")
      (node (ref "IC9") (pin "14") (pinfunction "4B_14") (pintype "bidirectional"))
      (node (ref "J37") (pin "24") (pinfunction "24_24") (pintype "bidirectional"))
      (node (ref "R170") (pin "2") (pinfunction "2_2") (pintype "passive"))
    )
    (net (code "36") (name "/LVDS7_P") (class "Default")
      (node (ref "IC9") (pin "13") (pinfunction "4A_13") (pintype "bidirectional"))
      (node (ref "J37") (pin "23") (pinfunction "23_23") (pintype "bidirectional"))
      (node (ref "R170") (pin "1") (pinfunction "1_1") (pintype "passive"))
    )
    (net (code "37") (name "/TERM_IO0") (class "Default")
      (node (ref "R1") (pin "1") (pinfunction "1_1") (pintype "passive"))
      (node (ref "SW1") (pin "8") (pinfunction "8_8") (pintype "passive"))
      (node (ref "T1") (pin "1") (pinfunction "G_1") (pintype "passive"))
    )
    (net (code "38") (name "/TERM_IO1") (class "Default")
      (node (ref "R2") (pin "1") (pinfunction "1_1") (pintype "passive"))
      (node (ref "SW1") (pin "7") (pinfunction "7_7") (pintype "passive"))
      (node (ref "T2") (pin "1") (pinfunction "G_1") (pintype "passive"))
    )
    (net (code "39") (name "/TERM_IO2") (class "Default")
      (node (ref "R3") (pin "1") (pinfunction "1_1") (pintype "passive"))
      (node (ref "SW1") (pin "6") (pinfunction "6_6") (pintype "passive"))
      (node (ref "T3") (pin "1") (pinfunction "G_1") (pintype "passive"))
    )
    (net (code "40") (name "/TERM_IO3") (class "Default")
      (node (ref "R4") (pin "1") (pinfunction "1_1") (pintype "passive"))
      (node (ref "SW1") (pin "5") (pinfunction "5_5") (pintype "passive"))
      (node (ref "T4") (pin "1") (pinfunction "G_1") (pintype "passive"))
    )
    (net (code "41") (name "/TERM_IO4") (class "Default")
      (node (ref "R5") (pin "1") (pinfunction "1_1") (pintype "passive"))
      (node (ref "SW2") (pin "8") (pinfunction "8_8") (pintype "passive"))
      (node (ref "T5") (pin "1") (pinfunction "G_1") (pintype "passive"))
    )
    (net (code "42") (name "/TERM_IO5") (class "Default")
      (node (ref "R7") (pin "1") (pinfunction "1_1") (pintype "passive"))
      (node (ref "SW2") (pin "7") (pinfunction "7_7") (pintype "passive"))
      (node (ref "T6") (pin "1") (pinfunction "G_1") (pintype "passive"))
    )
    (net (code "43") (name "/TERM_IO6") (class "Default")
      (node (ref "R9") (pin "1") (pinfunction "1_1") (pintype "passive"))
      (node (ref "SW2") (pin "6") (pinfunction "6_6") (pintype "passive"))
      (node (ref "T7") (pin "1") (pinfunction "G_1") (pintype "passive"))
    )
    (net (code "44") (name "/TERM_IO7") (class "Default")
      (node (ref "R11") (pin "1") (pinfunction "1_1") (pintype "passive"))
      (node (ref "SW2") (pin "5") (pinfunction "5_5") (pintype "passive"))
      (node (ref "T8") (pin "1") (pinfunction "G_1") (pintype "passive"))
    )
    (net (code "45") (name "GND") (class "Default")
      (node (ref "B1") (pin "1") (pinfunction "1_1") (pintype "bidirectional"))
      (node (ref "B2") (pin "1") (pinfunction "1_1") (pintype "bidirectional"))
      (node (ref "B4") (pin "1") (pinfunction "1_1") (pintype "bidirectional"))
      (node (ref "C14") (pin "1") (pinfunction "1_1") (pintype "passive"))
      (node (ref "C15") (pin "1") (pinfunction "1_1") (pintype "passive"))
      (node (ref "C16") (pin "1") (pinfunction "1_1") (pintype "passive"))
      (node (ref "C17") (pin "1") (pinfunction "1_1") (pintype "passive"))
      (node (ref "C18") (pin "2") (pinfunction "2_2") (pintype "passive"))
      (node (ref "C19") (pin "1") (pinfunction "1_1") (pintype "passive"))
      (node (ref "C20") (pin "1") (pinfunction "1_1") (pintype "passive"))
      (node (ref "C21") (pin "1") (pinfunction "1_1") (pintype "passive"))
      (node (ref "C22") (pin "1") (pinfunction "1_1") (pintype "passive"))
      (node (ref "C23") (pin "1") (pinfunction "1_1") (pintype "passive"))
      (node (ref "C24") (pin "1") (pinfunction "1_1") (pintype "passive"))
      (node (ref "C33") (pin "1") (pinfunction "1_1") (pintype "passive"))
      (node (ref "C34") (pin "2") (pinfunction "2_2") (pintype "passive"))
      (node (ref "C35") (pin "1") (pinfunction "1_1") (pintype "passive"))
      (node (ref "C36") (pin "2") (pinfunction "2_2") (pintype "passive"))
      (node (ref "C37") (pin "1") (pinfunction "1_1") (pintype "passive"))
      (node (ref "C38") (pin "1") (pinfunction "1_1") (pintype "passive"))
      (node (ref "C53") (pin "1") (pinfunction "1_1") (pintype "passive"))
      (node (ref "C54") (pin "1") (pinfunction "1_1") (pintype "passive"))
      (node (ref "C55") (pin "1") (pinfunction "1_1") (pintype "passive"))
      (node (ref "C56") (pin "1") (pinfunction "1_1") (pintype "passive"))
      (node (ref "C69") (pin "1") (pinfunction "1_1") (pintype "passive"))
      (node (ref "C70") (pin "1") (pinfunction "1_1") (pintype "passive"))
      (node (ref "C71") (pin "2") (pinfunction "2_2") (pintype "passive"))
      (node (ref "C72") (pin "1") (pinfunction "1_1") (pintype "passive"))
      (node (ref "C73") (pin "1") (pinfunction "1_1") (pintype "passive"))
      (node (ref "C74") (pin "1") (pinfunction "1_1") (pintype "passive"))
      (node (ref "C75") (pin "1") (pinfunction "1_1") (pintype "passive"))
      (node (ref "IC1") (pin "1") (pinfunction "-Vin_1") (pintype "power_in"))
      (node (ref "IC10") (pin "9") (pinfunction "GND2_9") (pintype "power_in"))
      (node (ref "IC11") (pin "8") (pinfunction "GND1_8") (pintype "power_in"))
      (node (ref "IC12") (pin "2") (pinfunction "-Vin_2") (pintype "power_in"))
      (node (ref "IC13") (pin "1") (pinfunction "A0_1") (pintype "input"))
      (node (ref "IC13") (pin "8") (pinfunction "GND_8") (pintype "power_in"))
      (node (ref "IC2") (pin "1") (pinfunction "-Vin_1") (pintype "power_in"))
      (node (ref "IC21") (pin "18") (pinfunction "GND_18") (pintype "power_in"))
      (node (ref "IC21") (pin "23") (pinfunction "GND_23") (pintype "power_in"))
      (node (ref "IC21") (pin "27") (pinfunction "GND_27") (pintype "power_in"))
      (node (ref "IC21") (pin "31") (pinfunction "GND_31") (pintype "power_in"))
      (node (ref "IC21") (pin "34") (pinfunction "GND_34") (pintype "power_in"))
      (node (ref "IC21") (pin "38") (pinfunction "GND_38") (pintype "power_in"))
      (node (ref "IC21") (pin "43") (pinfunction "GND_43") (pintype "power_in"))
      (node (ref "IC21") (pin "49") (pinfunction "EP_49") (pintype "power_in"))
      (node (ref "IC21") (pin "6") (pinfunction "GND_6") (pintype "power_in"))
      (node (ref "IC21") (pin "7") (pinfunction "GND_7") (pintype "power_in"))
      (node (ref "IC22") (pin "9") (pinfunction "GND2_9") (pintype "power_in"))
      (node (ref "IC28") (pin "8") (pinfunction "GND1_8") (pintype "power_in"))
      (node (ref "IC30") (pin "1") (pinfunction "PGND_1") (pintype "power_in"))
      (node (ref "IC30") (pin "11") (pinfunction "EP_11") (pintype "power_in"))
      (node (ref "IC30") (pin "6") (pinfunction "AGND_6") (pintype "power_in"))
      (node (ref "IC31") (pin "2") (pinfunction "-Vin_2") (pintype "power_in"))
      (node (ref "IC32") (pin "2") (pinfunction "VSS_2") (pintype "power_in"))
      (node (ref "IC9") (pin "18") (pinfunction "GND_18") (pintype "power_in"))
      (node (ref "IC9") (pin "23") (pinfunction "GND_23") (pintype "power_in"))
      (node (ref "IC9") (pin "27") (pinfunction "GND_27") (pintype "power_in"))
      (node (ref "IC9") (pin "31") (pinfunction "GND_31") (pintype "power_in"))
      (node (ref "IC9") (pin "34") (pinfunction "GND_34") (pintype "power_in"))
      (node (ref "IC9") (pin "38") (pinfunction "GND_38") (pintype "power_in"))
      (node (ref "IC9") (pin "43") (pinfunction "GND_43") (pintype "power_in"))
      (node (ref "IC9") (pin "49") (pinfunction "EP_49") (pintype "power_in"))
      (node (ref "IC9") (pin "6") (pinfunction "GND_6") (pintype "power_in"))
      (node (ref "IC9") (pin "7") (pinfunction "GND_7") (pintype "power_in"))
      (node (ref "J37") (pin "1") (pinfunction "1_1") (pintype "bidirectional"))
      (node (ref "J37") (pin "10") (pinfunction "10_10") (pintype "bidirectional"))
      (node (ref "J37") (pin "13") (pinfunction "13_13") (pintype "bidirectional"))
      (node (ref "J37") (pin "16") (pinfunction "16_16") (pintype "bidirectional"))
      (node (ref "J37") (pin "19") (pinfunction "19_19") (pintype "bidirectional"))
      (node (ref "J37") (pin "22") (pinfunction "22_22") (pintype "bidirectional"))
      (node (ref "J37") (pin "25") (pinfunction "25_25") (pintype "bidirectional"))
      (node (ref "J37") (pin "4") (pinfunction "4_4") (pintype "bidirectional"))
      (node (ref "J37") (pin "7") (pinfunction "7_7") (pintype "bidirectional"))
      (node (ref "LD4") (pin "1") (pinfunction "C_1") (pintype "passive"))
      (node (ref "LD7") (pin "1") (pinfunction "C_1") (pintype "passive"))
      (node (ref "LD9") (pin "1") (pinfunction "C_1") (pintype "passive"))
      (node (ref "R138") (pin "2") (pinfunction "2_2") (pintype "passive"))
      (node (ref "R152") (pin "2") (pinfunction "2_2") (pintype "passive"))
      (node (ref "R157") (pin "2") (pinfunction "2_2") (pintype "passive"))
      (node (ref "R171") (pin "2") (pinfunction "2_2") (pintype "passive"))
      (node (ref "R173") (pin "1") (pinfunction "1_1") (pintype "passive"))
      (node (ref "R18") (pin "2") (pinfunction "2_2") (pintype "passive"))
      (node (ref "R25") (pin "2") (pinfunction "2_2") (pintype "passive"))
      (node (ref "SW9") (pin "3") (pinfunction "3_3") (pintype "passive"))
      (node (ref "SW9") (pin "4") (pinfunction "4_4") (pintype "passive"))
      (node (ref "T26") (pin "2") (pinfunction "S_2") (pintype "passive"))
      (node (ref "T28") (pin "2") (pinfunction "S_2") (pintype "passive"))
    )
    (net (code "46") (name "GND_ISO1") (class "Default")
      (node (ref "B10") (pin "1") (pinfunction "1_1") (pintype "bidirectional"))
      (node (ref "C1") (pin "1") (pinfunction "1_1") (pintype "passive"))
      (node (ref "C2") (pin "1") (pinfunction "1_1") (pintype "passive"))
      (node (ref "C48") (pin "1") (pinfunction "1_1") (pintype "passive"))
      (node (ref "C49") (pin "1") (pinfunction "1_1") (pintype "passive"))
      (node (ref "C50") (pin "1") (pinfunction "1_1") (pintype "passive"))
      (node (ref "C51") (pin "1") (pinfunction "1_1") (pintype "passive"))
      (node (ref "C52") (pin "2") (pinfunction "2_2") (pintype "passive"))
      (node (ref "IC2") (pin "7") (pinfunction "-Vout_7") (pintype "power_in"))
      (node (ref "IC22") (pin "8") (pinfunction "GND1_8") (pintype "power_in"))
      (node (ref "IC28") (pin "11") (pinfunction "B5_11") (pintype "input"))
      (node (ref "IC28") (pin "9") (pinfunction "GND2_9") (pintype "power_in"))
      (node (ref "IC29") (pin "11") (pinfunction "GND_11") (pintype "power_in"))
      (node (ref "IC29") (pin "2") (pinfunction "GND_2") (pintype "power_in"))
      (node (ref "IC29") (pin "5") (pinfunction "GND_5") (pintype "power_in"))
      (node (ref "IC29") (pin "8") (pinfunction "GND_8") (pintype "power_in"))
      (node (ref "IC3") (pin "1") (pinfunction "VSS_1") (pintype "power_in"))
      (node (ref "IC31") (pin "4") (pinfunction "-Vout_4") (pintype "power_in"))
      (node (ref "J1") (pin "1") (pinfunction "1_1") (pintype "bidirectional"))
      (node (ref "J1") (pin "3") (pinfunction "3_3") (pintype "bidirectional"))
      (node (ref "J2") (pin "1") (pinfunction "1_1") (pintype "bidirectional"))
      (node (ref "J2") (pin "3") (pinfunction "3_3") (pintype "bidirectional"))
      (node (ref "LD1") (pin "1") (pinfunction "C_1") (pintype "passive"))
      (node (ref "LD1") (pin "3") (pinfunction "C_3") (pintype "passive"))
      (node (ref "LD2") (pin "1") (pinfunction "C_1") (pintype "passive"))
      (node (ref "LD2") (pin "3") (pinfunction "C_3") (pintype "passive"))
      (node (ref "R12") (pin "1") (pinfunction "1_1") (pintype "passive"))
      (node (ref "R140") (pin "1") (pinfunction "1_1") (pintype "passive"))
      (node (ref "R143") (pin "1") (pinfunction "1_1") (pintype "passive"))
      (node (ref "R146") (pin "1") (pinfunction "1_1") (pintype "passive"))
      (node (ref "R149") (pin "1") (pinfunction "1_1") (pintype "passive"))
      (node (ref "R18") (pin "1") (pinfunction "1_1") (pintype "passive"))
      (node (ref "T1") (pin "2") (pinfunction "S_2") (pintype "passive"))
      (node (ref "T2") (pin "2") (pinfunction "S_2") (pintype "passive"))
      (node (ref "T27") (pin "2") (pinfunction "S_2") (pintype "passive"))
      (node (ref "T3") (pin "2") (pinfunction "S_2") (pintype "passive"))
      (node (ref "T4") (pin "2") (pinfunction "S_2") (pintype "passive"))
    )
    (net (code "47") (name "GND_ISO2") (class "Default")
      (node (ref "B12") (pin "1") (pinfunction "1_1") (pintype "bidirectional"))
      (node (ref "C28") (pin "1") (pinfunction "1_1") (pintype "passive"))
      (node (ref "C29") (pin "1") (pinfunction "1_1") (pintype "passive"))
      (node (ref "C3") (pin "1") (pinfunction "1_1") (pintype "passive"))
      (node (ref "C30") (pin "1") (pinfunction "1_1") (pintype "passive"))
      (node (ref "C31") (pin "1") (pinfunction "1_1") (pintype "passive"))
      (node (ref "C32") (pin "2") (pinfunction "2_2") (pintype "passive"))
      (node (ref "C4") (pin "1") (pinfunction "1_1") (pintype "passive"))
      (node (ref "IC1") (pin "7") (pinfunction "-Vout_7") (pintype "power_in"))
      (node (ref "IC10") (pin "8") (pinfunction "GND1_8") (pintype "power_in"))
      (node (ref "IC11") (pin "11") (pinfunction "B5_11") (pintype "input"))
      (node (ref "IC11") (pin "9") (pinfunction "GND2_9") (pintype "power_in"))
      (node (ref "IC12") (pin "4") (pinfunction "-Vout_4") (pintype "power_in"))
      (node (ref "IC4") (pin "1") (pinfunction "VSS_1") (pintype "power_in"))
      (node (ref "IC8") (pin "11") (pinfunction "GND_11") (pintype "power_in"))
      (node (ref "IC8") (pin "2") (pinfunction "GND_2") (pintype "power_in"))
      (node (ref "IC8") (pin "5") (pinfunction "GND_5") (pintype "power_in"))
      (node (ref "IC8") (pin "8") (pinfunction "GND_8") (pintype "power_in"))
      (node (ref "J3") (pin "1") (pinfunction "1_1") (pintype "bidirectional"))
      (node (ref "J3") (pin "3") (pinfunction "3_3") (pintype "bidirectional"))
      (node (ref "J4") (pin "1") (pinfunction "1_1") (pintype "bidirectional"))
      (node (ref "J4") (pin "3") (pinfunction "3_3") (pintype "bidirectional"))
      (node (ref "LD3") (pin "1") (pinfunction "C_1") (pintype "passive"))
      (node (ref "LD3") (pin "3") (pinfunction "C_3") (pintype "passive"))
      (node (ref "LD8") (pin "1") (pinfunction "C_1") (pintype "passive"))
      (node (ref "LD8") (pin "3") (pinfunction "C_3") (pintype "passive"))
      (node (ref "R159") (pin "1") (pinfunction "1_1") (pintype "passive"))
      (node (ref "R162") (pin "1") (pinfunction "1_1") (pintype "passive"))
      (node (ref "R165") (pin "1") (pinfunction "1_1") (pintype "passive"))
      (node (ref "R169") (pin "1") (pinfunction "1_1") (pintype "passive"))
      (node (ref "R19") (pin "1") (pinfunction "1_1") (pintype "passive"))
      (node (ref "R25") (pin "1") (pinfunction "1_1") (pintype "passive"))
      (node (ref "T29") (pin "2") (pinfunction "S_2") (pintype "passive"))
      (node (ref "T5") (pin "2") (pinfunction "S_2") (pintype "passive"))
      (node (ref "T6") (pin "2") (pinfunction "S_2") (pintype "passive"))
      (node (ref "T7") (pin "2") (pinfunction "S_2") (pintype "passive"))
      (node (ref "T8") (pin "2") (pinfunction "S_2") (pintype "passive"))
    )
    (net (code "48") (name "Net-(IC1-+Vout)") (class "Default")
      (node (ref "C4") (pin "2") (pinfunction "2_2") (pintype "passive"))
      (node (ref "IC1") (pin "8") (pinfunction "+Vout_8") (pintype "power_in"))
      (node (ref "IC12") (pin "6") (pinfunction "+Vout_6") (pintype "power_in"))
      (node (ref "L3") (pin "2") (pinfunction "2_2") (pintype "passive"))
    )
    (net (code "49") (name "Net-(IC2-+Vout)") (class "Default")
      (node (ref "C1") (pin "2") (pinfunction "2_2") (pintype "passive"))
      (node (ref "IC2") (pin "8") (pinfunction "+Vout_8") (pintype "power_in"))
      (node (ref "IC31") (pin "6") (pinfunction "+Vout_6") (pintype "power_in"))
      (node (ref "L2") (pin "2") (pinfunction "2_2") (pintype "passive"))
    )
    (net (code "50") (name "Net-(IC4-RST)") (class "Default")
      (node (ref "IC4") (pin "2") (pinfunction "RST_2") (pintype "output"))
      (node (ref "IC8") (pin "13") (pinfunction "OE_13") (pintype "input"))
      (node (ref "R19") (pin "2") (pinfunction "2_2") (pintype "passive"))
    )
    (net (code "51") (name "Net-(IC8-A1)") (class "Default")
      (node (ref "IC8") (pin "1") (pinfunction "A1_1") (pintype "bidirectional"))
      (node (ref "IC8") (pin "3") (pinfunction "A2_3") (pintype "bidirectional"))
      (node (ref "R169") (pin "2") (pinfunction "2_2") (pintype "passive"))
      (node (ref "R23") (pin "2") (pinfunction "2_2") (pintype "passive"))
    )
    (net (code "52") (name "Net-(IC8-A3)") (class "Default")
      (node (ref "IC8") (pin "4") (pinfunction "A3_4") (pintype "bidirectional"))
      (node (ref "IC8") (pin "6") (pinfunction "A4_6") (pintype "bidirectional"))
      (node (ref "R165") (pin "2") (pinfunction "2_2") (pintype "passive"))
      (node (ref "R22") (pin "2") (pinfunction "2_2") (pintype "passive"))
    )
    (net (code "53") (name "Net-(IC8-A5)") (class "Default")
      (node (ref "IC8") (pin "7") (pinfunction "A5_7") (pintype "bidirectional"))
      (node (ref "IC8") (pin "9") (pinfunction "A6_9") (pintype "bidirectional"))
      (node (ref "R162") (pin "2") (pinfunction "2_2") (pintype "passive"))
      (node (ref "R21") (pin "2") (pinfunction "2_2") (pintype "passive"))
    )
    (net (code "54") (name "Net-(IC8-A7)") (class "Default")
      (node (ref "IC8") (pin "10") (pinfunction "A7_10") (pintype "bidirectional"))
      (node (ref "IC8") (pin "12") (pinfunction "A8_12") (pintype "bidirectional"))
      (node (ref "R159") (pin "2") (pinfunction "2_2") (pintype "passive"))
      (node (ref "R20") (pin "2") (pinfunction "2_2") (pintype "passive"))
    )
    (net (code "55") (name "Net-(IC8-DIR)") (class "Default")
      (node (ref "IC8") (pin "24") (pinfunction "DIR_24") (pintype "input"))
      (node (ref "R172") (pin "1") (pinfunction "1_1") (pintype "passive"))
      (node (ref "T29") (pin "3") (pinfunction "D_3") (pintype "passive"))
    )
    (net (code "56") (name "Net-(IC9-1FSEN)") (class "Default")
      (node (ref "IC9") (pin "20") (pinfunction "3FSEN_20") (pintype "input"))
      (node (ref "IC9") (pin "22") (pinfunction "4FSEN_22") (pintype "input"))
      (node (ref "IC9") (pin "39") (pinfunction "1FSEN_39") (pintype "input"))
      (node (ref "IC9") (pin "41") (pinfunction "2FSEN_41") (pintype "input"))
      (node (ref "R157") (pin "1") (pinfunction "1_1") (pintype "passive"))
      (node (ref "R171") (pin "1") (pinfunction "1_1") (pintype "passive"))
    )
    (net (code "57") (name "Net-(IC10-A1)") (class "Default")
      (node (ref "IC10") (pin "2") (pinfunction "A1_2") (pintype "input"))
      (node (ref "IC11") (pin "15") (pinfunction "B1_15") (pintype "output"))
      (node (ref "IC8") (pin "14") (pinfunction "B8_14") (pintype "bidirectional"))
      (node (ref "IC8") (pin "15") (pinfunction "B7_15") (pintype "bidirectional"))
    )
    (net (code "58") (name "Net-(IC10-A2)") (class "Default")
      (node (ref "IC10") (pin "3") (pinfunction "A2_3") (pintype "input"))
      (node (ref "IC11") (pin "14") (pinfunction "B2_14") (pintype "output"))
      (node (ref "IC8") (pin "17") (pinfunction "B6_17") (pintype "bidirectional"))
      (node (ref "IC8") (pin "18") (pinfunction "B5_18") (pintype "bidirectional"))
    )
    (net (code "59") (name "Net-(IC10-A3)") (class "Default")
      (node (ref "IC10") (pin "4") (pinfunction "A3_4") (pintype "input"))
      (node (ref "IC11") (pin "13") (pinfunction "B3_13") (pintype "output"))
      (node (ref "IC8") (pin "19") (pinfunction "B4_19") (pintype "bidirectional"))
      (node (ref "IC8") (pin "20") (pinfunction "B3_20") (pintype "bidirectional"))
    )
    (net (code "60") (name "Net-(IC10-A4)") (class "Default")
      (node (ref "IC10") (pin "5") (pinfunction "A4_5") (pintype "input"))
      (node (ref "IC11") (pin "12") (pinfunction "B4_12") (pintype "output"))
      (node (ref "IC8") (pin "22") (pinfunction "B2_22") (pintype "bidirectional"))
      (node (ref "IC8") (pin "23") (pinfunction "B1_23") (pintype "bidirectional"))
    )
    (net (code "61") (name "Net-(IC10-A5)") (class "Default")
      (node (ref "IC10") (pin "6") (pinfunction "A5_6") (pintype "output"))
      (node (ref "R24") (pin "1") (pinfunction "1_1") (pintype "passive"))
      (node (ref "T29") (pin "1") (pinfunction "G_1") (pintype "passive"))
    )
    (net (code "62") (name "Net-(IC10-B1)") (class "Default")
      (node (ref "IC10") (pin "15") (pinfunction "B1_15") (pintype "output"))
      (node (ref "IC9") (pin "35") (pinfunction "1D_35") (pintype "input"))
    )
    (net (code "63") (name "Net-(IC10-B2)") (class "Default")
      (node (ref "IC10") (pin "14") (pinfunction "B2_14") (pintype "output"))
      (node (ref "IC9") (pin "32") (pinfunction "2D_32") (pintype "input"))
    )
    (net (code "64") (name "Net-(IC10-B3)") (class "Default")
      (node (ref "IC10") (pin "13") (pinfunction "B3_13") (pintype "output"))
      (node (ref "IC9") (pin "28") (pinfunction "3D_28") (pintype "input"))
    )
    (net (code "65") (name "Net-(IC10-B4)") (class "Default")
      (node (ref "IC10") (pin "12") (pinfunction "B4_12") (pintype "output"))
      (node (ref "IC9") (pin "25") (pinfunction "4D_25") (pintype "input"))
    )
    (net (code "66") (name "Net-(IC10-B5)") (class "Default")
      (node (ref "IC10") (pin "11") (pinfunction "B5_11") (pintype "input"))
      (node (ref "R154") (pin "2") (pinfunction "2_2") (pintype "passive"))
      (node (ref "R155") (pin "1") (pinfunction "1_1") (pintype "passive"))
      (node (ref "T28") (pin "3") (pinfunction "D_3") (pintype "passive"))
    )
    (net (code "67") (name "Net-(IC11-A1)") (class "Default")
      (node (ref "IC11") (pin "2") (pinfunction "A1_2") (pintype "input"))
      (node (ref "IC9") (pin "36") (pinfunction "1R_36") (pintype "output"))
    )
    (net (code "68") (name "Net-(IC11-A2)") (class "Default")
      (node (ref "IC11") (pin "3") (pinfunction "A2_3") (pintype "input"))
      (node (ref "IC9") (pin "33") (pinfunction "2R_33") (pintype "output"))
    )
    (net (code "69") (name "Net-(IC11-A3)") (class "Default")
      (node (ref "IC11") (pin "4") (pinfunction "A3_4") (pintype "input"))
      (node (ref "IC9") (pin "29") (pinfunction "3R_29") (pintype "output"))
    )
    (net (code "70") (name "Net-(IC11-A4)") (class "Default")
      (node (ref "IC11") (pin "5") (pinfunction "A4_5") (pintype "input"))
      (node (ref "IC9") (pin "26") (pinfunction "4R_26") (pintype "output"))
    )
    (net (code "71") (name "Net-(IC11-EN2)") (class "Default")
      (node (ref "IC11") (pin "10") (pinfunction "EN2_10") (pintype "input"))
      (node (ref "R24") (pin "2") (pinfunction "2_2") (pintype "passive"))
    )
    (net (code "72") (name "Net-(IC21-1D)") (class "Default")
      (node (ref "IC21") (pin "35") (pinfunction "1D_35") (pintype "input"))
      (node (ref "IC22") (pin "15") (pinfunction "B1_15") (pintype "output"))
    )
    (net (code "73") (name "Net-(IC21-1FSEN)") (class "Default")
      (node (ref "IC21") (pin "20") (pinfunction "3FSEN_20") (pintype "input"))
      (node (ref "IC21") (pin "22") (pinfunction "4FSEN_22") (pintype "input"))
      (node (ref "IC21") (pin "39") (pinfunction "1FSEN_39") (pintype "input"))
      (node (ref "IC21") (pin "41") (pinfunction "2FSEN_41") (pintype "input"))
      (node (ref "R138") (pin "1") (pinfunction "1_1") (pintype "passive"))
      (node (ref "R152") (pin "1") (pinfunction "1_1") (pintype "passive"))
    )
    (net (code "74") (name "Net-(IC21-1R)") (class "Default")
      (node (ref "IC21") (pin "36") (pinfunction "1R_36") (pintype "output"))
      (node (ref "IC28") (pin "2") (pinfunction "A1_2") (pintype "input"))
    )
    (net (code "75") (name "Net-(IC21-2D)") (class "Default")
      (node (ref "IC21") (pin "32") (pinfunction "2D_32") (pintype "input"))
      (node (ref "IC22") (pin "14") (pinfunction "B2_14") (pintype "output"))
    )
    (net (code "76") (name "Net-(IC21-2R)") (class "Default")
      (node (ref "IC21") (pin "33") (pinfunction "2R_33") (pintype "output"))
      (node (ref "IC28") (pin "3") (pinfunction "A2_3") (pintype "input"))
    )
    (net (code "77") (name "Net-(IC21-3D)") (class "Default")
      (node (ref "IC21") (pin "28") (pinfunction "3D_28") (pintype "input"))
      (node (ref "IC22") (pin "13") (pinfunction "B3_13") (pintype "output"))
    )
    (net (code "78") (name "Net-(IC21-3R)") (class "Default")
      (node (ref "IC21") (pin "29") (pinfunction "3R_29") (pintype "output"))
      (node (ref "IC28") (pin "4") (pinfunction "A3_4") (pintype "input"))
    )
    (net (code "79") (name "Net-(IC21-4D)") (class "Default")
      (node (ref "IC21") (pin "25") (pinfunction "4D_25") (pintype "input"))
      (node (ref "IC22") (pin "12") (pinfunction "B4_12") (pintype "output"))
    )
    (net (code "80") (name "Net-(IC21-4R)") (class "Default")
      (node (ref "IC21") (pin "26") (pinfunction "4R_26") (pintype "output"))
      (node (ref "IC28") (pin "5") (pinfunction "A4_5") (pintype "input"))
    )
    (net (code "81") (name "Net-(IC22-A1)") (class "Default")
      (node (ref "IC22") (pin "2") (pinfunction "A1_2") (pintype "input"))
      (node (ref "IC28") (pin "15") (pinfunction "B1_15") (pintype "output"))
      (node (ref "IC29") (pin "14") (pinfunction "B8_14") (pintype "bidirectional"))
      (node (ref "IC29") (pin "15") (pinfunction "B7_15") (pintype "bidirectional"))
    )
    (net (code "82") (name "Net-(IC22-A2)") (class "Default")
      (node (ref "IC22") (pin "3") (pinfunction "A2_3") (pintype "input"))
      (node (ref "IC28") (pin "14") (pinfunction "B2_14") (pintype "output"))
      (node (ref "IC29") (pin "17") (pinfunction "B6_17") (pintype "bidirectional"))
      (node (ref "IC29") (pin "18") (pinfunction "B5_18") (pintype "bidirectional"))
    )
    (net (code "83") (name "Net-(IC22-A3)") (class "Default")
      (node (ref "IC22") (pin "4") (pinfunction "A3_4") (pintype "input"))
      (node (ref "IC28") (pin "13") (pinfunction "B3_13") (pintype "output"))
      (node (ref "IC29") (pin "19") (pinfunction "B4_19") (pintype "bidirectional"))
      (node (ref "IC29") (pin "20") (pinfunction "B3_20") (pintype "bidirectional"))
    )
    (net (code "84") (name "Net-(IC22-A4)") (class "Default")
      (node (ref "IC22") (pin "5") (pinfunction "A4_5") (pintype "input"))
      (node (ref "IC28") (pin "12") (pinfunction "B4_12") (pintype "output"))
      (node (ref "IC29") (pin "22") (pinfunction "B2_22") (pintype "bidirectional"))
      (node (ref "IC29") (pin "23") (pinfunction "B1_23") (pintype "bidirectional"))
    )
    (net (code "85") (name "Net-(IC22-A5)") (class "Default")
      (node (ref "IC22") (pin "6") (pinfunction "A5_6") (pintype "output"))
      (node (ref "R17") (pin "1") (pinfunction "1_1") (pintype "passive"))
      (node (ref "T27") (pin "1") (pinfunction "G_1") (pintype "passive"))
    )
    (net (code "86") (name "Net-(IC22-B5)") (class "Default")
      (node (ref "IC22") (pin "11") (pinfunction "B5_11") (pintype "input"))
      (node (ref "R135") (pin "2") (pinfunction "2_2") (pintype "passive"))
      (node (ref "R136") (pin "1") (pinfunction "1_1") (pintype "passive"))
      (node (ref "T26") (pin "3") (pinfunction "D_3") (pintype "passive"))
    )
    (net (code "87") (name "Net-(IC28-EN2)") (class "Default")
      (node (ref "IC28") (pin "10") (pinfunction "EN2_10") (pintype "input"))
      (node (ref "R17") (pin "2") (pinfunction "2_2") (pintype "passive"))
    )
    (net (code "88") (name "Net-(IC29-A1)") (class "Default")
      (node (ref "IC29") (pin "1") (pinfunction "A1_1") (pintype "bidirectional"))
      (node (ref "IC29") (pin "3") (pinfunction "A2_3") (pintype "bidirectional"))
      (node (ref "R149") (pin "2") (pinfunction "2_2") (pintype "passive"))
      (node (ref "R16") (pin "2") (pinfunction "2_2") (pintype "passive"))
    )
    (net (code "89") (name "Net-(IC29-A3)") (class "Default")
      (node (ref "IC29") (pin "4") (pinfunction "A3_4") (pintype "bidirectional"))
      (node (ref "IC29") (pin "6") (pinfunction "A4_6") (pintype "bidirectional"))
      (node (ref "R146") (pin "2") (pinfunction "2_2") (pintype "passive"))
      (node (ref "R15") (pin "2") (pinfunction "2_2") (pintype "passive"))
    )
    (net (code "90") (name "Net-(IC29-A5)") (class "Default")
      (node (ref "IC29") (pin "7") (pinfunction "A5_7") (pintype "bidirectional"))
      (node (ref "IC29") (pin "9") (pinfunction "A6_9") (pintype "bidirectional"))
      (node (ref "R14") (pin "2") (pinfunction "2_2") (pintype "passive"))
      (node (ref "R143") (pin "2") (pinfunction "2_2") (pintype "passive"))
    )
    (net (code "91") (name "Net-(IC29-A7)") (class "Default")
      (node (ref "IC29") (pin "10") (pinfunction "A7_10") (pintype "bidirectional"))
      (node (ref "IC29") (pin "12") (pinfunction "A8_12") (pintype "bidirectional"))
      (node (ref "R13") (pin "2") (pinfunction "2_2") (pintype "passive"))
      (node (ref "R140") (pin "2") (pinfunction "2_2") (pintype "passive"))
    )
    (net (code "92") (name "Net-(IC29-DIR)") (class "Default")
      (node (ref "IC29") (pin "24") (pinfunction "DIR_24") (pintype "input"))
      (node (ref "R150") (pin "1") (pinfunction "1_1") (pintype "passive"))
      (node (ref "T27") (pin "3") (pinfunction "D_3") (pintype "passive"))
    )
    (net (code "93") (name "Net-(IC29-OE)") (class "Default")
      (node (ref "IC29") (pin "13") (pinfunction "OE_13") (pintype "input"))
      (node (ref "IC3") (pin "2") (pinfunction "RST_2") (pintype "output"))
      (node (ref "R12") (pin "2") (pinfunction "2_2") (pintype "passive"))
    )
    (net (code "94") (name "Net-(IC30-FB)") (class "Default")
      (node (ref "IC30") (pin "5") (pinfunction "FB_5") (pintype "input"))
      (node (ref "R167") (pin "1") (pinfunction "1_1") (pintype "passive"))
      (node (ref "R173") (pin "2") (pinfunction "2_2") (pintype "passive"))
    )
    (net (code "95") (name "Net-(IC30-SW)") (class "Default")
      (node (ref "IC30") (pin "9") (pinfunction "SW_9") (pintype "output"))
      (node (ref "L1") (pin "1") (pinfunction "1_1") (pintype "passive"))
    )
    (net (code "96") (name "Net-(LD4-A)") (class "Default")
      (node (ref "LD4") (pin "2") (pinfunction "A_2") (pintype "passive"))
      (node (ref "R6") (pin "1") (pinfunction "1_1") (pintype "passive"))
    )
    (net (code "97") (name "Net-(LD5A-C)") (class "Default")
      (node (ref "LD5") (pin "1") (pinfunction "C_1") (pintype "passive"))
      (node (ref "R134") (pin "1") (pinfunction "1_1") (pintype "passive"))
    )
    (net (code "98") (name "Net-(LD5B-C)") (class "Default")
      (node (ref "LD5") (pin "3") (pinfunction "C_3") (pintype "passive"))
      (node (ref "R135") (pin "1") (pinfunction "1_1") (pintype "passive"))
    )
    (net (code "99") (name "Net-(LD6A-C)") (class "Default")
      (node (ref "LD6") (pin "1") (pinfunction "C_1") (pintype "passive"))
      (node (ref "R153") (pin "1") (pinfunction "1_1") (pintype "passive"))
    )
    (net (code "100") (name "Net-(LD6B-C)") (class "Default")
      (node (ref "LD6") (pin "3") (pinfunction "C_3") (pintype "passive"))
      (node (ref "R154") (pin "1") (pinfunction "1_1") (pintype "passive"))
    )
    (net (code "101") (name "Net-(LD7-A)") (class "Default")
      (node (ref "LD7") (pin "2") (pinfunction "A_2") (pintype "passive"))
      (node (ref "R8") (pin "2") (pinfunction "2_2") (pintype "passive"))
    )
    (net (code "102") (name "Net-(LD9-A)") (class "Default")
      (node (ref "LD9") (pin "2") (pinfunction "A_2") (pintype "passive"))
      (node (ref "R10") (pin "2") (pinfunction "2_2") (pintype "passive"))
    )
    (net (code "103") (name "Net-(T1-D)") (class "Default")
      (node (ref "R139") (pin "1") (pinfunction "1_1") (pintype "passive"))
      (node (ref "T1") (pin "3") (pinfunction "D_3") (pintype "passive"))
    )
    (net (code "104") (name "Net-(T2-D)") (class "Default")
      (node (ref "R142") (pin "1") (pinfunction "1_1") (pintype "passive"))
      (node (ref "T2") (pin "3") (pinfunction "D_3") (pintype "passive"))
    )
    (net (code "105") (name "Net-(T3-D)") (class "Default")
      (node (ref "R145") (pin "1") (pinfunction "1_1") (pintype "passive"))
      (node (ref "T3") (pin "3") (pinfunction "D_3") (pintype "passive"))
    )
    (net (code "106") (name "Net-(T4-D)") (class "Default")
      (node (ref "R148") (pin "1") (pinfunction "1_1") (pintype "passive"))
      (node (ref "T4") (pin "3") (pinfunction "D_3") (pintype "passive"))
    )
    (net (code "107") (name "Net-(T5-D)") (class "Default")
      (node (ref "R158") (pin "1") (pinfunction "1_1") (pintype "passive"))
      (node (ref "T5") (pin "3") (pinfunction "D_3") (pintype "passive"))
    )
    (net (code "108") (name "Net-(T6-D)") (class "Default")
      (node (ref "R161") (pin "1") (pinfunction "1_1") (pintype "passive"))
      (node (ref "T6") (pin "3") (pinfunction "D_3") (pintype "passive"))
    )
    (net (code "109") (name "Net-(T7-D)") (class "Default")
      (node (ref "R164") (pin "1") (pinfunction "1_1") (pintype "passive"))
      (node (ref "T7") (pin "3") (pinfunction "D_3") (pintype "passive"))
    )
    (net (code "110") (name "Net-(T8-D)") (class "Default")
      (node (ref "R168") (pin "1") (pinfunction "1_1") (pintype "passive"))
      (node (ref "T8") (pin "3") (pinfunction "D_3") (pintype "passive"))
    )
    (net (code "111") (name "P3V3") (class "Default")
      (node (ref "B5") (pin "1") (pinfunction "1_1") (pintype "bidirectional"))
      (node (ref "C14") (pin "2") (pinfunction "2_2") (pintype "passive"))
      (node (ref "C15") (pin "2") (pinfunction "2_2") (pintype "passive"))
      (node (ref "C16") (pin "2") (pinfunction "2_2") (pintype "passive"))
      (node (ref "C17") (pin "2") (pinfunction "2_2") (pintype "passive"))
      (node (ref "C18") (pin "1") (pinfunction "1_1") (pintype "passive"))
      (node (ref "C19") (pin "2") (pinfunction "2_2") (pintype "passive"))
      (node (ref "C20") (pin "2") (pinfunction "2_2") (pintype "passive"))
      (node (ref "C21") (pin "2") (pinfunction "2_2") (pintype "passive"))
      (node (ref "C22") (pin "2") (pinfunction "2_2") (pintype "passive"))
      (node (ref "C23") (pin "2") (pinfunction "2_2") (pintype "passive"))
      (node (ref "C24") (pin "2") (pinfunction "2_2") (pintype "passive"))
      (node (ref "C53") (pin "2") (pinfunction "2_2") (pintype "passive"))
      (node (ref "C54") (pin "2") (pinfunction "2_2") (pintype "passive"))
      (node (ref "C55") (pin "2") (pinfunction "2_2") (pintype "passive"))
      (node (ref "C56") (pin "2") (pinfunction "2_2") (pintype "passive"))
      (node (ref "C69") (pin "2") (pinfunction "2_2") (pintype "passive"))
      (node (ref "C70") (pin "2") (pinfunction "2_2") (pintype "passive"))
      (node (ref "C71") (pin "1") (pinfunction "1_1") (pintype "passive"))
      (node (ref "C72") (pin "2") (pinfunction "2_2") (pintype "passive"))
      (node (ref "C73") (pin "2") (pinfunction "2_2") (pintype "passive"))
      (node (ref "IC10") (pin "10") (pinfunction "EN2_10") (pintype "input"))
      (node (ref "IC10") (pin "16") (pinfunction "VDD2_16") (pintype "power_in"))
      (node (ref "IC11") (pin "1") (pinfunction "VDD1_1") (pintype "power_in"))
      (node (ref "IC11") (pin "7") (pinfunction "EN1_7") (pintype "input"))
      (node (ref "IC21") (pin "11") (pinfunction "VCC_11") (pintype "power_in"))
      (node (ref "IC21") (pin "15") (pinfunction "VCC_15") (pintype "power_in"))
      (node (ref "IC21") (pin "16") (pinfunction "VCC_16") (pintype "power_in"))
      (node (ref "IC21") (pin "2") (pinfunction "VCC_2") (pintype "power_in"))
      (node (ref "IC21") (pin "24") (pinfunction "VCC_24") (pintype "power_in"))
      (node (ref "IC21") (pin "30") (pinfunction "PDN_30") (pintype "input"))
      (node (ref "IC21") (pin "37") (pinfunction "VCC_37") (pintype "power_in"))
      (node (ref "IC21") (pin "45") (pinfunction "VCC_45") (pintype "power_in"))
      (node (ref "IC21") (pin "46") (pinfunction "VCC_46") (pintype "power_in"))
      (node (ref "IC22") (pin "10") (pinfunction "EN2_10") (pintype "input"))
      (node (ref "IC22") (pin "16") (pinfunction "VDD2_16") (pintype "power_in"))
      (node (ref "IC28") (pin "1") (pinfunction "VDD1_1") (pintype "power_in"))
      (node (ref "IC28") (pin "7") (pinfunction "EN1_7") (pintype "input"))
      (node (ref "IC30") (pin "10") (pinfunction "VOS_10") (pintype "input"))
      (node (ref "IC30") (pin "8") (pinfunction "SLEEP_8") (pintype "input"))
      (node (ref "IC9") (pin "11") (pinfunction "VCC_11") (pintype "power_in"))
      (node (ref "IC9") (pin "15") (pinfunction "VCC_15") (pintype "power_in"))
      (node (ref "IC9") (pin "16") (pinfunction "VCC_16") (pintype "power_in"))
      (node (ref "IC9") (pin "2") (pinfunction "VCC_2") (pintype "power_in"))
      (node (ref "IC9") (pin "24") (pinfunction "VCC_24") (pintype "power_in"))
      (node (ref "IC9") (pin "30") (pinfunction "PDN_30") (pintype "input"))
      (node (ref "IC9") (pin "37") (pinfunction "VCC_37") (pintype "power_in"))
      (node (ref "IC9") (pin "45") (pinfunction "VCC_45") (pintype "power_in"))
      (node (ref "IC9") (pin "46") (pinfunction "VCC_46") (pintype "power_in"))
      (node (ref "L1") (pin "2") (pinfunction "2_2") (pintype "passive"))
      (node (ref "LD5") (pin "2") (pinfunction "A_2") (pintype "passive"))
      (node (ref "LD5") (pin "4") (pinfunction "A_4") (pintype "passive"))
      (node (ref "LD6") (pin "2") (pinfunction "A_2") (pintype "passive"))
      (node (ref "LD6") (pin "4") (pinfunction "A_4") (pintype "passive"))
      (node (ref "R136") (pin "2") (pinfunction "2_2") (pintype "passive"))
      (node (ref "R137") (pin "2") (pinfunction "2_2") (pintype "passive"))
      (node (ref "R155") (pin "2") (pinfunction "2_2") (pintype "passive"))
      (node (ref "R156") (pin "2") (pinfunction "2_2") (pintype "passive"))
      (node (ref "R167") (pin "2") (pinfunction "2_2") (pintype "passive"))
      (node (ref "R8") (pin "1") (pinfunction "1_1") (pintype "passive"))
    )
    (net (code "112") (name "P3V3_MP") (class "Default")
      (node (ref "B3") (pin "1") (pinfunction "1_1") (pintype "bidirectional"))
      (node (ref "C37") (pin "2") (pinfunction "2_2") (pintype "passive"))
      (node (ref "C38") (pin "2") (pinfunction "2_2") (pintype "passive"))
      (node (ref "IC13") (pin "16") (pinfunction "VCC_16") (pintype "bidirectional"))
      (node (ref "IC13") (pin "2") (pinfunction "A1_2") (pintype "input"))
      (node (ref "IC13") (pin "3") (pinfunction "A2_3") (pintype "input"))
      (node (ref "IC32") (pin "4") (pinfunction "VCC_4") (pintype "power_in"))
      (node (ref "J37") (pin "30") (pinfunction "30_30") (pintype "bidirectional"))
      (node (ref "R10") (pin "1") (pinfunction "1_1") (pintype "passive"))
    )
    (net (code "113") (name "P5V0_ISO1") (class "Default")
      (node (ref "B9") (pin "1") (pinfunction "1_1") (pintype "bidirectional"))
      (node (ref "C2") (pin "2") (pinfunction "2_2") (pintype "passive"))
      (node (ref "C48") (pin "2") (pinfunction "2_2") (pintype "passive"))
      (node (ref "C49") (pin "2") (pinfunction "2_2") (pintype "passive"))
      (node (ref "C50") (pin "2") (pinfunction "2_2") (pintype "passive"))
      (node (ref "C51") (pin "2") (pinfunction "2_2") (pintype "passive"))
      (node (ref "C52") (pin "1") (pinfunction "1_1") (pintype "passive"))
      (node (ref "IC22") (pin "1") (pinfunction "VDD1_1") (pintype "power_in"))
      (node (ref "IC22") (pin "7") (pinfunction "EN1_7") (pintype "input"))
      (node (ref "IC28") (pin "16") (pinfunction "VDD2_16") (pintype "power_in"))
      (node (ref "IC29") (pin "16") (pinfunction "VCC_16") (pintype "power_in"))
      (node (ref "IC29") (pin "21") (pinfunction "VCC_21") (pintype "power_in"))
      (node (ref "IC3") (pin "3") (pinfunction "VDD_3") (pintype "power_in"))
      (node (ref "L2") (pin "1") (pinfunction "1_1") (pintype "passive"))
      (node (ref "R150") (pin "2") (pinfunction "2_2") (pintype "passive"))
      (node (ref "SW1") (pin "1") (pinfunction "1_1") (pintype "passive"))
      (node (ref "SW1") (pin "2") (pinfunction "2_2") (pintype "passive"))
      (node (ref "SW1") (pin "3") (pinfunction "3_3") (pintype "passive"))
      (node (ref "SW1") (pin "4") (pinfunction "4_4") (pintype "passive"))
    )
    (net (code "114") (name "P5V0_ISO2") (class "Default")
      (node (ref "B11") (pin "1") (pinfunction "1_1") (pintype "bidirectional"))
      (node (ref "C28") (pin "2") (pinfunction "2_2") (pintype "passive"))
      (node (ref "C29") (pin "2") (pinfunction "2_2") (pintype "passive"))
      (node (ref "C3") (pin "2") (pinfunction "2_2") (pintype "passive"))
      (node (ref "C30") (pin "2") (pinfunction "2_2") (pintype "passive"))
      (node (ref "C31") (pin "2") (pinfunction "2_2") (pintype "passive"))
      (node (ref "C32") (pin "1") (pinfunction "1_1") (pintype "passive"))
      (node (ref "IC10") (pin "1") (pinfunction "VDD1_1") (pintype "power_in"))
      (node (ref "IC10") (pin "7") (pinfunction "EN1_7") (pintype "input"))
      (node (ref "IC11") (pin "16") (pinfunction "VDD2_16") (pintype "power_in"))
      (node (ref "IC4") (pin "3") (pinfunction "VDD_3") (pintype "power_in"))
      (node (ref "IC8") (pin "16") (pinfunction "VCC_16") (pintype "power_in"))
      (node (ref "IC8") (pin "21") (pinfunction "VCC_21") (pintype "power_in"))
      (node (ref "L3") (pin "1") (pinfunction "1_1") (pintype "passive"))
      (node (ref "R172") (pin "2") (pinfunction "2_2") (pintype "passive"))
      (node (ref "SW2") (pin "1") (pinfunction "1_1") (pintype "passive"))
      (node (ref "SW2") (pin "2") (pinfunction "2_2") (pintype "passive"))
      (node (ref "SW2") (pin "3") (pinfunction "3_3") (pintype "passive"))
      (node (ref "SW2") (pin "4") (pinfunction "4_4") (pintype "passive"))
    )
    (net (code "115") (name "P12V0") (class "Default")
      (node (ref "B6") (pin "1") (pinfunction "1_1") (pintype "bidirectional"))
      (node (ref "C33") (pin "2") (pinfunction "2_2") (pintype "passive"))
      (node (ref "C34") (pin "1") (pinfunction "1_1") (pintype "passive"))
      (node (ref "C35") (pin "2") (pinfunction "2_2") (pintype "passive"))
      (node (ref "C36") (pin "1") (pinfunction "1_1") (pintype "passive"))
      (node (ref "C74") (pin "2") (pinfunction "2_2") (pintype "passive"))
      (node (ref "C75") (pin "2") (pinfunction "2_2") (pintype "passive"))
      (node (ref "IC1") (pin "3") (pinfunction "+Vin_3") (pintype "power_in"))
      (node (ref "IC12") (pin "1") (pinfunction "+Vin_1") (pintype "power_in"))
      (node (ref "IC2") (pin "3") (pinfunction "+Vin_3") (pintype "power_in"))
      (node (ref "IC30") (pin "2") (pinfunction "VIN_2") (pintype "input"))
      (node (ref "IC30") (pin "3") (pinfunction "EN_3") (pintype "input"))
      (node (ref "IC31") (pin "1") (pinfunction "+Vin_1") (pintype "power_in"))
      (node (ref "J37") (pin "28") (pinfunction "28_28") (pintype "bidirectional"))
      (node (ref "J37") (pin "29") (pinfunction "29_29") (pintype "bidirectional"))
      (node (ref "R6") (pin "2") (pinfunction "2_2") (pintype "passive"))
    )
    (net (code "116") (name "unconnected-(IC1-na-Pad14)") (class "Default")
      (node (ref "IC1") (pin "14") (pinfunction "na_14") (pintype "passive"))
    )
    (net (code "117") (name "unconnected-(IC2-na-Pad14)") (class "Default")
      (node (ref "IC2") (pin "14") (pinfunction "na_14") (pintype "passive"))
    )
    (net (code "118") (name "unconnected-(IC9-NC-Pad17)") (class "Default")
      (node (ref "IC9") (pin "17") (pinfunction "NC_17") (pintype "passive"))
    )
    (net (code "119") (name "unconnected-(IC9-NC-Pad44)") (class "Default")
      (node (ref "IC9") (pin "44") (pinfunction "NC_44") (pintype "passive"))
    )
    (net (code "120") (name "unconnected-(IC11-A5-Pad6)") (class "Default")
      (node (ref "IC11") (pin "6") (pinfunction "A5_6") (pintype "output"))
    )
    (net (code "121") (name "unconnected-(IC13-~{INT}-Pad13)") (class "Default")
      (node (ref "IC13") (pin "13") (pinfunction "~{INT}_13") (pintype "output"))
    )
    (net (code "122") (name "unconnected-(IC21-NC-Pad17)") (class "Default")
      (node (ref "IC21") (pin "17") (pinfunction "NC_17") (pintype "passive"))
    )
    (net (code "123") (name "unconnected-(IC21-NC-Pad44)") (class "Default")
      (node (ref "IC21") (pin "44") (pinfunction "NC_44") (pintype "passive"))
    )
    (net (code "124") (name "unconnected-(IC28-A5-Pad6)") (class "Default")
      (node (ref "IC28") (pin "6") (pinfunction "A5_6") (pintype "output"))
    )
    (net (code "125") (name "unconnected-(IC30-NC-Pad4)") (class "Default")
      (node (ref "IC30") (pin "4") (pinfunction "NC_4") (pintype "passive"))
    )
    (net (code "126") (name "unconnected-(IC30-PG-Pad7)") (class "Default")
      (node (ref "IC30") (pin "7") (pinfunction "PG_7") (pintype "output"))
    )
    (net (code "127") (name "unconnected-(IC32-NC-Pad5)") (class "Default")
      (node (ref "IC32") (pin "5") (pinfunction "NC_5") (pintype "passive"))
    )
  )
)
